# axiom_beta_sensor_cmv12000_v0_9_d0ae0354.net
KiCad netlist of a schematic drawn in EAGLE
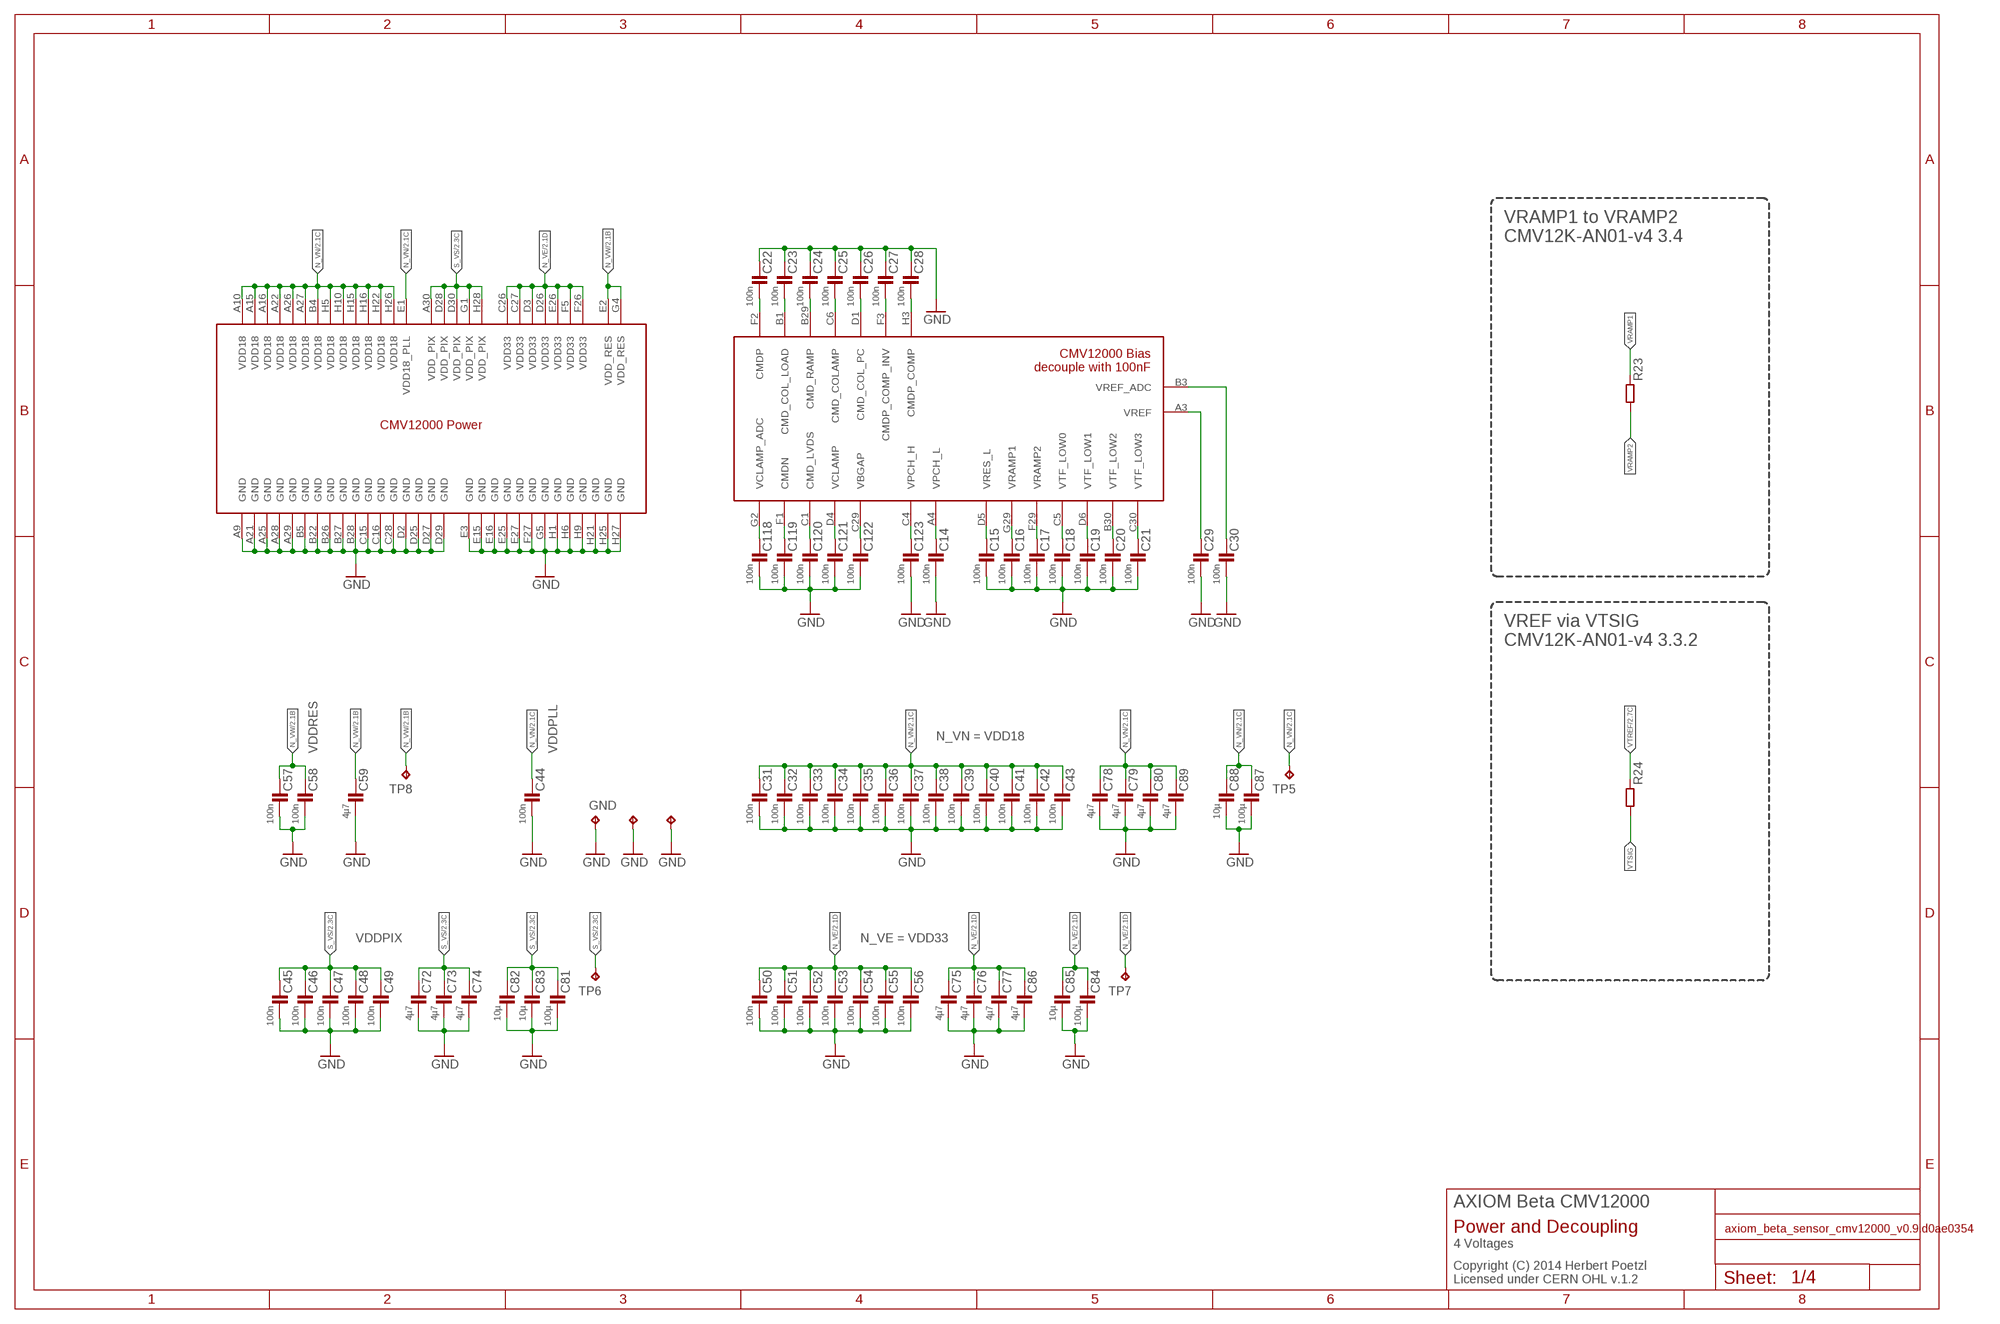
[diagram p0: schematic, sheet 1]
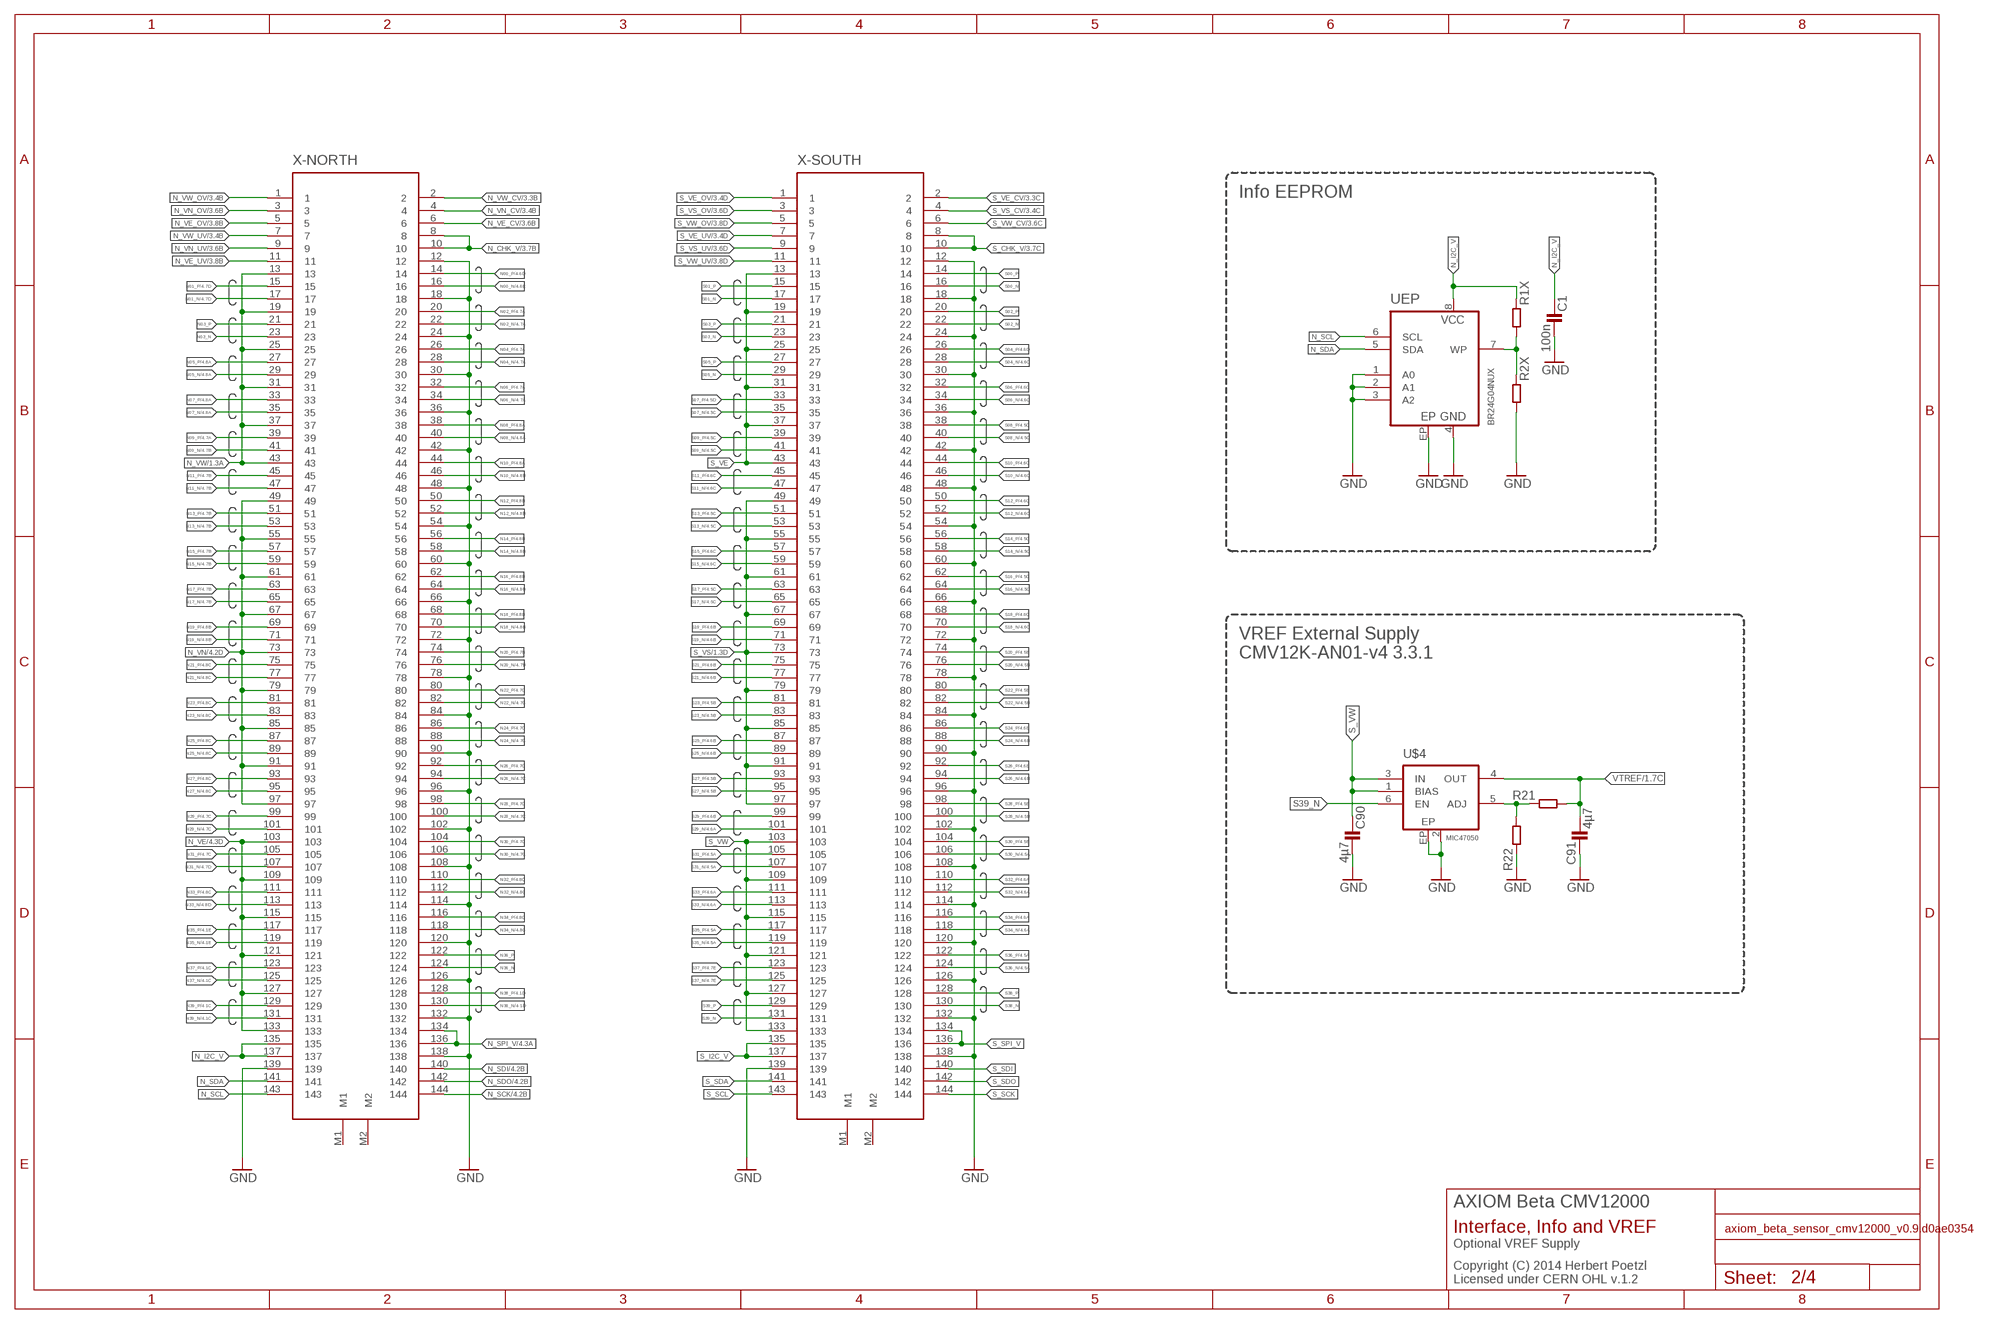
[diagram p1: schematic, sheet 2]
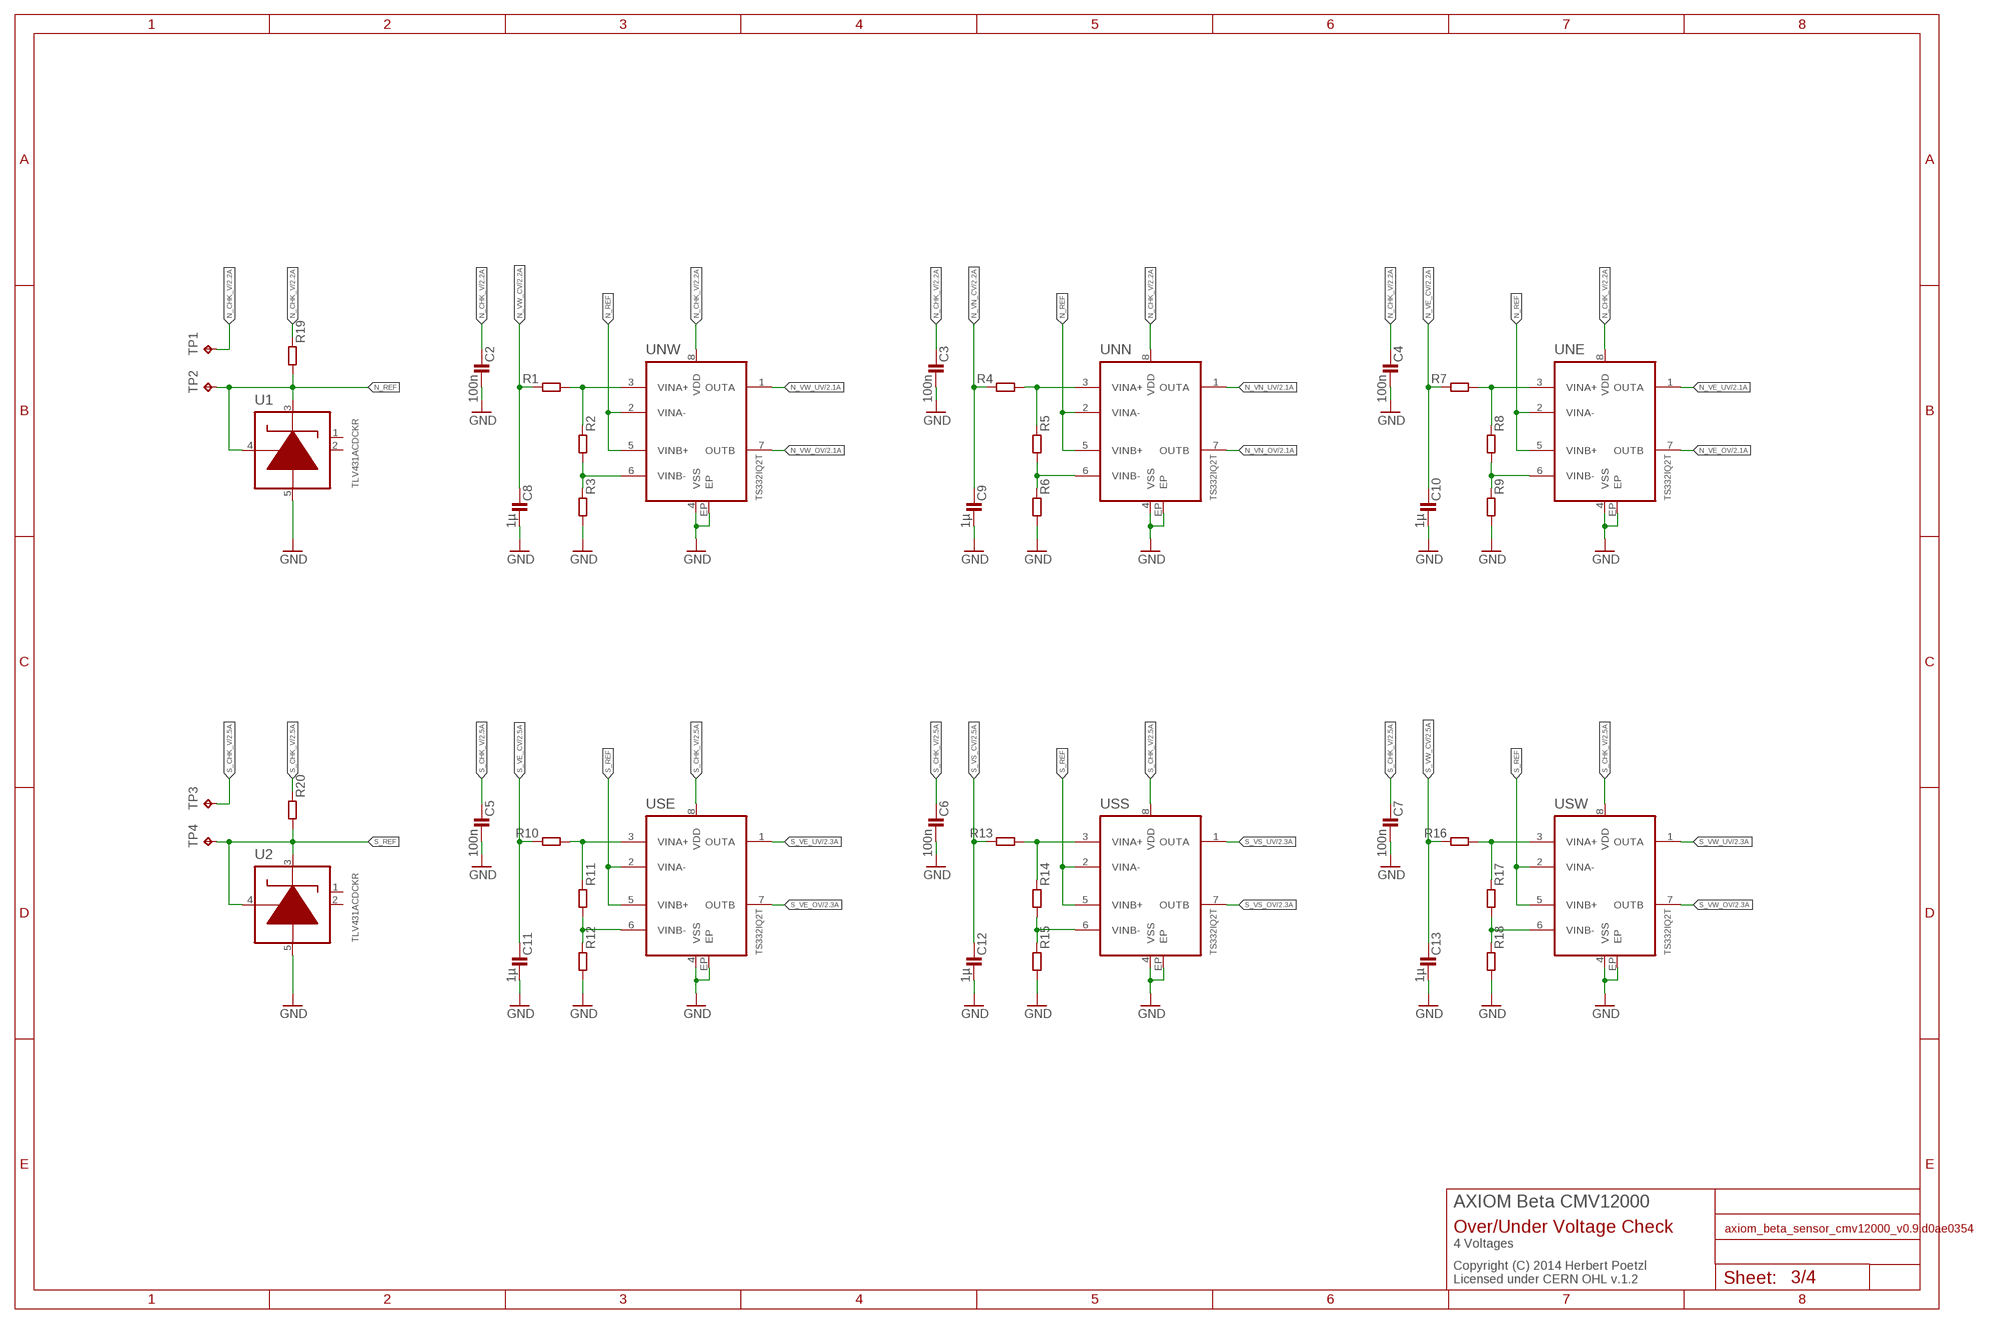
[diagram p2: schematic, sheet 3]
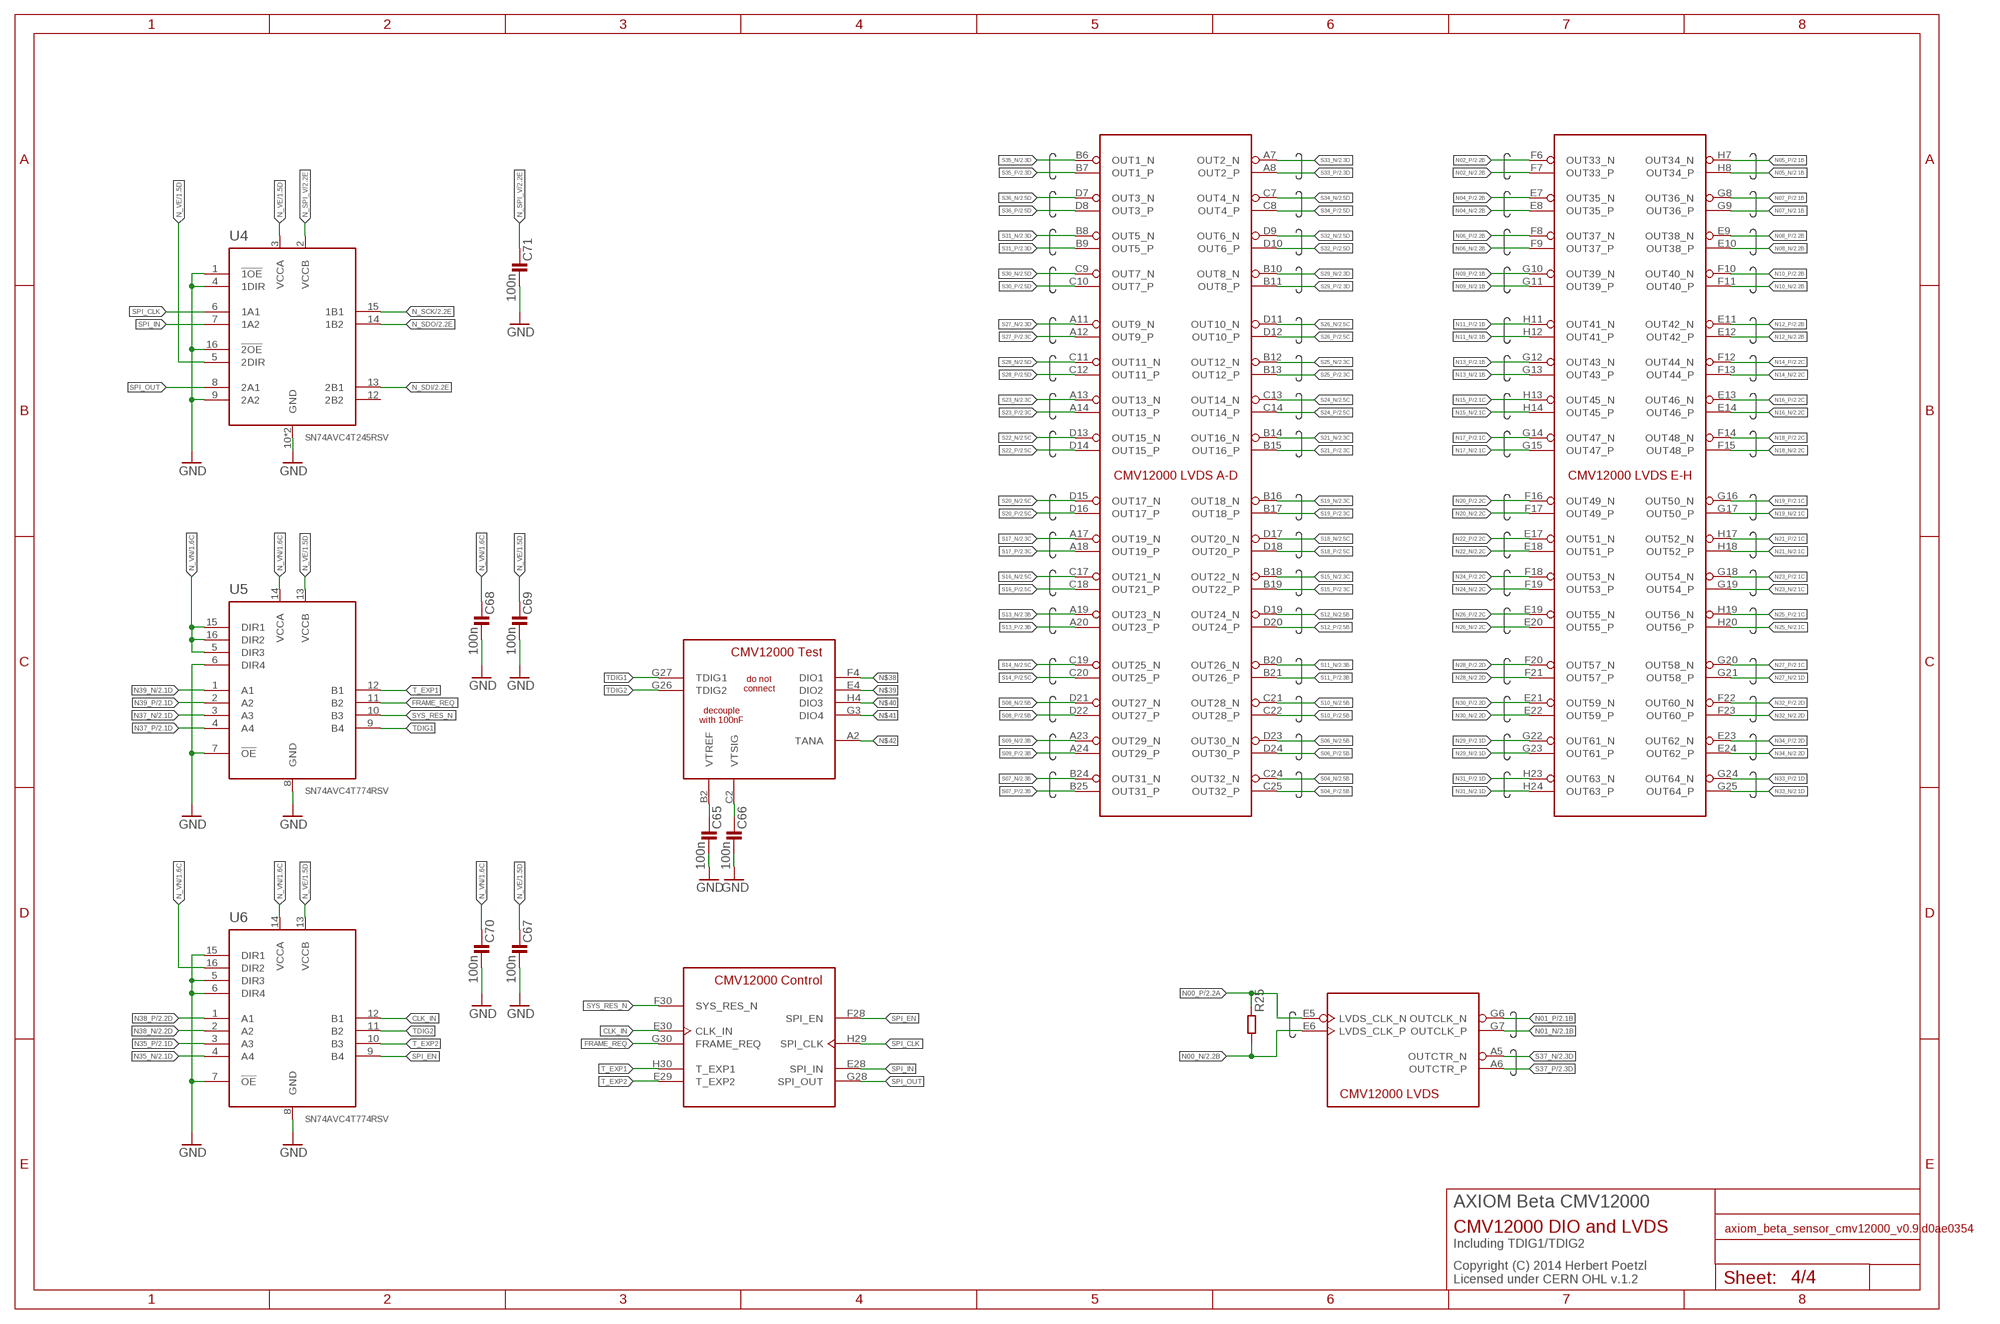
[diagram p3: schematic, sheet 4]

(export (version "E")
  (design (tool "Eeschema 10.0.6"))
  (components
    (comp (ref "C2")
      (value "100n")
      (footprint "eagle-import:0402-C")
      (libsource (lib "eagle-import") (part "C0402-C"))
    )
    (comp (ref "C3")
      (value "100n")
      (footprint "eagle-import:0402-C")
      (libsource (lib "eagle-import") (part "C0402-C"))
    )
    (comp (ref "C4")
      (value "100n")
      (footprint "eagle-import:0402-C")
      (libsource (lib "eagle-import") (part "C0402-C"))
    )
    (comp (ref "C5")
      (value "100n")
      (footprint "eagle-import:0402-C")
      (libsource (lib "eagle-import") (part "C0402-C"))
    )
    (comp (ref "C6")
      (value "100n")
      (footprint "eagle-import:0402-C")
      (libsource (lib "eagle-import") (part "C0402-C"))
    )
    (comp (ref "C7")
      (value "100n")
      (footprint "eagle-import:0402-C")
      (libsource (lib "eagle-import") (part "C0402-C"))
    )
    (comp (ref "C8")
      (value "1µ")
      (footprint "eagle-import:0402-C")
      (libsource (lib "eagle-import") (part "C0402-C"))
    )
    (comp (ref "C9")
      (value "1µ")
      (footprint "eagle-import:0402-C")
      (libsource (lib "eagle-import") (part "C0402-C"))
    )
    (comp (ref "C10")
      (value "1µ")
      (footprint "eagle-import:0402-C")
      (libsource (lib "eagle-import") (part "C0402-C"))
    )
    (comp (ref "C11")
      (value "1µ")
      (footprint "eagle-import:0402-C")
      (libsource (lib "eagle-import") (part "C0402-C"))
    )
    (comp (ref "C12")
      (value "1µ")
      (footprint "eagle-import:0402-C")
      (libsource (lib "eagle-import") (part "C0402-C"))
    )
    (comp (ref "C13")
      (value "1µ")
      (footprint "eagle-import:0402-C")
      (libsource (lib "eagle-import") (part "C0402-C"))
    )
    (comp (ref "R1")
      (value "R0402-C")
      (footprint "eagle-import:0402-C")
      (libsource (lib "eagle-import") (part "R0402-C"))
    )
    (comp (ref "R2")
      (value "R0402-C")
      (footprint "eagle-import:0402-C")
      (libsource (lib "eagle-import") (part "R0402-C"))
    )
    (comp (ref "R3")
      (value "R0402-C")
      (footprint "eagle-import:0402-C")
      (libsource (lib "eagle-import") (part "R0402-C"))
    )
    (comp (ref "R4")
      (value "R0402-C")
      (footprint "eagle-import:0402-C")
      (libsource (lib "eagle-import") (part "R0402-C"))
    )
    (comp (ref "R5")
      (value "R0402-C")
      (footprint "eagle-import:0402-C")
      (libsource (lib "eagle-import") (part "R0402-C"))
    )
    (comp (ref "R6")
      (value "R0402-C")
      (footprint "eagle-import:0402-C")
      (libsource (lib "eagle-import") (part "R0402-C"))
    )
    (comp (ref "R7")
      (value "R0402-C")
      (footprint "eagle-import:0402-C")
      (libsource (lib "eagle-import") (part "R0402-C"))
    )
    (comp (ref "R8")
      (value "R0402-C")
      (footprint "eagle-import:0402-C")
      (libsource (lib "eagle-import") (part "R0402-C"))
    )
    (comp (ref "R9")
      (value "R0402-C")
      (footprint "eagle-import:0402-C")
      (libsource (lib "eagle-import") (part "R0402-C"))
    )
    (comp (ref "R10")
      (value "R0402-C")
      (footprint "eagle-import:0402-C")
      (libsource (lib "eagle-import") (part "R0402-C"))
    )
    (comp (ref "R11")
      (value "R0402-C")
      (footprint "eagle-import:0402-C")
      (libsource (lib "eagle-import") (part "R0402-C"))
    )
    (comp (ref "R12")
      (value "R0402-C")
      (footprint "eagle-import:0402-C")
      (libsource (lib "eagle-import") (part "R0402-C"))
    )
    (comp (ref "R13")
      (value "R0402-C")
      (footprint "eagle-import:0402-C")
      (libsource (lib "eagle-import") (part "R0402-C"))
    )
    (comp (ref "R14")
      (value "R0402-C")
      (footprint "eagle-import:0402-C")
      (libsource (lib "eagle-import") (part "R0402-C"))
    )
    (comp (ref "R15")
      (value "R0402-C")
      (footprint "eagle-import:0402-C")
      (libsource (lib "eagle-import") (part "R0402-C"))
    )
    (comp (ref "R16")
      (value "R0402-C")
      (footprint "eagle-import:0402-C")
      (libsource (lib "eagle-import") (part "R0402-C"))
    )
    (comp (ref "R17")
      (value "R0402-C")
      (footprint "eagle-import:0402-C")
      (libsource (lib "eagle-import") (part "R0402-C"))
    )
    (comp (ref "R18")
      (value "R0402-C")
      (footprint "eagle-import:0402-C")
      (libsource (lib "eagle-import") (part "R0402-C"))
    )
    (comp (ref "R19")
      (value "R0402-C")
      (footprint "eagle-import:0402-C")
      (libsource (lib "eagle-import") (part "R0402-C"))
    )
    (comp (ref "R20")
      (value "R0402-C")
      (footprint "eagle-import:0402-C")
      (libsource (lib "eagle-import") (part "R0402-C"))
    )
    (comp (ref "TP1")
      (value "TPTP10R")
      (footprint "eagle-import:TP10R")
      (libsource (lib "eagle-import") (part "TPTP10R"))
    )
    (comp (ref "TP2")
      (value "TPTP10R")
      (footprint "eagle-import:TP10R")
      (libsource (lib "eagle-import") (part "TPTP10R"))
    )
    (comp (ref "TP3")
      (value "TPTP10R")
      (footprint "eagle-import:TP10R")
      (libsource (lib "eagle-import") (part "TPTP10R"))
    )
    (comp (ref "TP4")
      (value "TPTP10R")
      (footprint "eagle-import:TP10R")
      (libsource (lib "eagle-import") (part "TPTP10R"))
    )
    (comp (ref "U1")
      (value "TLV431ACDCKR")
      (footprint "eagle-import:SOT65P210X110-5N")
      (libsource (lib "eagle-import") (part "TLV431ACDCKR"))
    )
    (comp (ref "U2")
      (value "TLV431ACDCKR")
      (footprint "eagle-import:SOT65P210X110-5N")
      (libsource (lib "eagle-import") (part "TLV431ACDCKR"))
    )
    (comp (ref "UNE")
      (value "TS332IQ2T")
      (footprint "eagle-import:DFN200X200X100-9N")
      (libsource (lib "eagle-import") (part "TS332IQ2T"))
    )
    (comp (ref "UNN")
      (value "TS332IQ2T")
      (footprint "eagle-import:DFN200X200X100-9N")
      (libsource (lib "eagle-import") (part "TS332IQ2T"))
    )
    (comp (ref "UNW")
      (value "TS332IQ2T")
      (footprint "eagle-import:DFN200X200X100-9N")
      (libsource (lib "eagle-import") (part "TS332IQ2T"))
    )
    (comp (ref "USE")
      (value "TS332IQ2T")
      (footprint "eagle-import:DFN200X200X100-9N")
      (libsource (lib "eagle-import") (part "TS332IQ2T"))
    )
    (comp (ref "USS")
      (value "TS332IQ2T")
      (footprint "eagle-import:DFN200X200X100-9N")
      (libsource (lib "eagle-import") (part "TS332IQ2T"))
    )
    (comp (ref "USW")
      (value "TS332IQ2T")
      (footprint "eagle-import:DFN200X200X100-9N")
      (libsource (lib "eagle-import") (part "TS332IQ2T"))
    )
    (comp (ref "C65")
      (value "100n")
      (footprint "eagle-import:0402-C")
      (libsource (lib "eagle-import") (part "C0402-C"))
    )
    (comp (ref "C66")
      (value "100n")
      (footprint "eagle-import:0402-C")
      (libsource (lib "eagle-import") (part "C0402-C"))
    )
    (comp (ref "C67")
      (value "100n")
      (footprint "eagle-import:0402-C")
      (libsource (lib "eagle-import") (part "C0402-C"))
    )
    (comp (ref "C68")
      (value "100n")
      (footprint "eagle-import:0402-C")
      (libsource (lib "eagle-import") (part "C0402-C"))
    )
    (comp (ref "C69")
      (value "100n")
      (footprint "eagle-import:0402-C")
      (libsource (lib "eagle-import") (part "C0402-C"))
    )
    (comp (ref "C70")
      (value "100n")
      (footprint "eagle-import:0402-C")
      (libsource (lib "eagle-import") (part "C0402-C"))
    )
    (comp (ref "C71")
      (value "100n")
      (footprint "eagle-import:0402-C")
      (libsource (lib "eagle-import") (part "C0402-C"))
    )
    (comp (ref "R25")
      (value "R0402-C")
      (footprint "eagle-import:0402-C")
      (libsource (lib "eagle-import") (part "R0402-C"))
    )
    (comp (ref "U$2")
      (value "CMV12000ANDON")
      (footprint "eagle-import:10-30-07-237-400T4")
      (libsource (lib "eagle-import") (part "CMV12000ANDON"))
    )
    (comp (ref "U4")
      (value "SN74AVC4T245RSV")
      (footprint "eagle-import:QFN40P185X265X55-16N")
      (libsource (lib "eagle-import") (part "SN74AVC4T245RSV"))
    )
    (comp (ref "U5")
      (value "SN74AVC4T774RSV")
      (footprint "eagle-import:QFN40P185X265X55-16N")
      (libsource (lib "eagle-import") (part "SN74AVC4T774RSV"))
    )
    (comp (ref "U6")
      (value "SN74AVC4T774RSV")
      (footprint "eagle-import:QFN40P185X265X55-16N")
      (libsource (lib "eagle-import") (part "SN74AVC4T774RSV"))
    )
    (comp (ref "C1")
      (value "100n")
      (footprint "eagle-import:0402-C")
      (libsource (lib "eagle-import") (part "C0402-C"))
    )
    (comp (ref "C90")
      (value "4µ7")
      (footprint "eagle-import:0402-C")
      (libsource (lib "eagle-import") (part "C0402-C"))
    )
    (comp (ref "C91")
      (value "4µ7")
      (footprint "eagle-import:0402-C")
      (libsource (lib "eagle-import") (part "C0402-C"))
    )
    (comp (ref "R1X")
      (value "R0402-C")
      (footprint "eagle-import:0402-C")
      (libsource (lib "eagle-import") (part "R0402-C"))
    )
    (comp (ref "R2X")
      (value "R0402-C")
      (footprint "eagle-import:0402-C")
      (libsource (lib "eagle-import") (part "R0402-C"))
    )
    (comp (ref "R21")
      (value "R0402-C")
      (footprint "eagle-import:0402-C")
      (libsource (lib "eagle-import") (part "R0402-C"))
    )
    (comp (ref "R22")
      (value "R0402-C")
      (footprint "eagle-import:0402-C")
      (libsource (lib "eagle-import") (part "R0402-C"))
    )
    (comp (ref "U$4")
      (value "MIC47050")
      (footprint "eagle-import:MLF-6")
      (libsource (lib "eagle-import") (part "MIC47050-ADJ"))
    )
    (comp (ref "UEP")
      (value "BR24G04NUX")
      (footprint "eagle-import:DFN200X300X100-9N")
      (libsource (lib "eagle-import") (part "BR24G04NUX"))
    )
    (comp (ref "X-NORTH")
      (value "FX10-144P")
      (footprint "eagle-import:FX10A-144P")
      (libsource (lib "eagle-import") (part "FX10-144P"))
    )
    (comp (ref "X-SOUTH")
      (value "FX10-144P")
      (footprint "eagle-import:FX10A-144P")
      (libsource (lib "eagle-import") (part "FX10-144P"))
    )
    (comp (ref "C14")
      (value "100n")
      (footprint "eagle-import:0402-C")
      (libsource (lib "eagle-import") (part "C0402-C"))
    )
    (comp (ref "C15")
      (value "100n")
      (footprint "eagle-import:0402-C")
      (libsource (lib "eagle-import") (part "C0402-C"))
    )
    (comp (ref "C16")
      (value "100n")
      (footprint "eagle-import:0402-C")
      (libsource (lib "eagle-import") (part "C0402-C"))
    )
    (comp (ref "C17")
      (value "100n")
      (footprint "eagle-import:0402-C")
      (libsource (lib "eagle-import") (part "C0402-C"))
    )
    (comp (ref "C18")
      (value "100n")
      (footprint "eagle-import:0402-C")
      (libsource (lib "eagle-import") (part "C0402-C"))
    )
    (comp (ref "C19")
      (value "100n")
      (footprint "eagle-import:0402-C")
      (libsource (lib "eagle-import") (part "C0402-C"))
    )
    (comp (ref "C20")
      (value "100n")
      (footprint "eagle-import:0402-C")
      (libsource (lib "eagle-import") (part "C0402-C"))
    )
    (comp (ref "C21")
      (value "100n")
      (footprint "eagle-import:0402-C")
      (libsource (lib "eagle-import") (part "C0402-C"))
    )
    (comp (ref "C22")
      (value "100n")
      (footprint "eagle-import:0402-C")
      (libsource (lib "eagle-import") (part "C0402-C"))
    )
    (comp (ref "C23")
      (value "100n")
      (footprint "eagle-import:0402-C")
      (libsource (lib "eagle-import") (part "C0402-C"))
    )
    (comp (ref "C24")
      (value "100n")
      (footprint "eagle-import:0402-C")
      (libsource (lib "eagle-import") (part "C0402-C"))
    )
    (comp (ref "C25")
      (value "100n")
      (footprint "eagle-import:0402-C")
      (libsource (lib "eagle-import") (part "C0402-C"))
    )
    (comp (ref "C26")
      (value "100n")
      (footprint "eagle-import:0402-C")
      (libsource (lib "eagle-import") (part "C0402-C"))
    )
    (comp (ref "C27")
      (value "100n")
      (footprint "eagle-import:0402-C")
      (libsource (lib "eagle-import") (part "C0402-C"))
    )
    (comp (ref "C28")
      (value "100n")
      (footprint "eagle-import:0402-C")
      (libsource (lib "eagle-import") (part "C0402-C"))
    )
    (comp (ref "C29")
      (value "100n")
      (footprint "eagle-import:0402-C")
      (libsource (lib "eagle-import") (part "C0402-C"))
    )
    (comp (ref "C30")
      (value "100n")
      (footprint "eagle-import:0402-C")
      (libsource (lib "eagle-import") (part "C0402-C"))
    )
    (comp (ref "C31")
      (value "100n")
      (footprint "eagle-import:0402-C")
      (libsource (lib "eagle-import") (part "C0402-C"))
    )
    (comp (ref "C32")
      (value "100n")
      (footprint "eagle-import:0402-C")
      (libsource (lib "eagle-import") (part "C0402-C"))
    )
    (comp (ref "C33")
      (value "100n")
      (footprint "eagle-import:0402-C")
      (libsource (lib "eagle-import") (part "C0402-C"))
    )
    (comp (ref "C34")
      (value "100n")
      (footprint "eagle-import:0402-C")
      (libsource (lib "eagle-import") (part "C0402-C"))
    )
    (comp (ref "C35")
      (value "100n")
      (footprint "eagle-import:0402-C")
      (libsource (lib "eagle-import") (part "C0402-C"))
    )
    (comp (ref "C36")
      (value "100n")
      (footprint "eagle-import:0402-C")
      (libsource (lib "eagle-import") (part "C0402-C"))
    )
    (comp (ref "C37")
      (value "100n")
      (footprint "eagle-import:0402-C")
      (libsource (lib "eagle-import") (part "C0402-C"))
    )
    (comp (ref "C38")
      (value "100n")
      (footprint "eagle-import:0402-C")
      (libsource (lib "eagle-import") (part "C0402-C"))
    )
    (comp (ref "C39")
      (value "100n")
      (footprint "eagle-import:0402-C")
      (libsource (lib "eagle-import") (part "C0402-C"))
    )
    (comp (ref "C40")
      (value "100n")
      (footprint "eagle-import:0402-C")
      (libsource (lib "eagle-import") (part "C0402-C"))
    )
    (comp (ref "C41")
      (value "100n")
      (footprint "eagle-import:0402-C")
      (libsource (lib "eagle-import") (part "C0402-C"))
    )
    (comp (ref "C42")
      (value "100n")
      (footprint "eagle-import:0402-C")
      (libsource (lib "eagle-import") (part "C0402-C"))
    )
    (comp (ref "C43")
      (value "100n")
      (footprint "eagle-import:0402-C")
      (libsource (lib "eagle-import") (part "C0402-C"))
    )
    (comp (ref "C44")
      (value "100n")
      (footprint "eagle-import:0402-C")
      (libsource (lib "eagle-import") (part "C0402-C"))
    )
    (comp (ref "C45")
      (value "100n")
      (footprint "eagle-import:0402-C")
      (libsource (lib "eagle-import") (part "C0402-C"))
    )
    (comp (ref "C46")
      (value "100n")
      (footprint "eagle-import:0402-C")
      (libsource (lib "eagle-import") (part "C0402-C"))
    )
    (comp (ref "C47")
      (value "100n")
      (footprint "eagle-import:0402-C")
      (libsource (lib "eagle-import") (part "C0402-C"))
    )
    (comp (ref "C48")
      (value "100n")
      (footprint "eagle-import:0402-C")
      (libsource (lib "eagle-import") (part "C0402-C"))
    )
    (comp (ref "C49")
      (value "100n")
      (footprint "eagle-import:0402-C")
      (libsource (lib "eagle-import") (part "C0402-C"))
    )
    (comp (ref "C50")
      (value "100n")
      (footprint "eagle-import:0402-C")
      (libsource (lib "eagle-import") (part "C0402-C"))
    )
    (comp (ref "C51")
      (value "100n")
      (footprint "eagle-import:0402-C")
      (libsource (lib "eagle-import") (part "C0402-C"))
    )
    (comp (ref "C52")
      (value "100n")
      (footprint "eagle-import:0402-C")
      (libsource (lib "eagle-import") (part "C0402-C"))
    )
    (comp (ref "C53")
      (value "100n")
      (footprint "eagle-import:0402-C")
      (libsource (lib "eagle-import") (part "C0402-C"))
    )
    (comp (ref "C54")
      (value "100n")
      (footprint "eagle-import:0402-C")
      (libsource (lib "eagle-import") (part "C0402-C"))
    )
    (comp (ref "C55")
      (value "100n")
      (footprint "eagle-import:0402-C")
      (libsource (lib "eagle-import") (part "C0402-C"))
    )
    (comp (ref "C56")
      (value "100n")
      (footprint "eagle-import:0402-C")
      (libsource (lib "eagle-import") (part "C0402-C"))
    )
    (comp (ref "C57")
      (value "100n")
      (footprint "eagle-import:0402-C")
      (libsource (lib "eagle-import") (part "C0402-C"))
    )
    (comp (ref "C58")
      (value "100n")
      (footprint "eagle-import:0402-C")
      (libsource (lib "eagle-import") (part "C0402-C"))
    )
    (comp (ref "C59")
      (value "4µ7")
      (footprint "eagle-import:0402-C")
      (libsource (lib "eagle-import") (part "C0402-C"))
    )
    (comp (ref "C72")
      (value "4µ7")
      (footprint "eagle-import:0402-B")
      (libsource (lib "eagle-import") (part "C0402-B"))
    )
    (comp (ref "C73")
      (value "4µ7")
      (footprint "eagle-import:0402-C")
      (libsource (lib "eagle-import") (part "C0402-C"))
    )
    (comp (ref "C74")
      (value "4µ7")
      (footprint "eagle-import:0402-C")
      (libsource (lib "eagle-import") (part "C0402-C"))
    )
    (comp (ref "C75")
      (value "4µ7")
      (footprint "eagle-import:0402-C")
      (libsource (lib "eagle-import") (part "C0402-C"))
    )
    (comp (ref "C76")
      (value "4µ7")
      (footprint "eagle-import:0402-C")
      (libsource (lib "eagle-import") (part "C0402-C"))
    )
    (comp (ref "C77")
      (value "4µ7")
      (footprint "eagle-import:0402-B")
      (libsource (lib "eagle-import") (part "C0402-B"))
    )
    (comp (ref "C78")
      (value "4µ7")
      (footprint "eagle-import:0402-B")
      (libsource (lib "eagle-import") (part "C0402-B"))
    )
    (comp (ref "C79")
      (value "4µ7")
      (footprint "eagle-import:0402-C")
      (libsource (lib "eagle-import") (part "C0402-C"))
    )
    (comp (ref "C80")
      (value "4µ7")
      (footprint "eagle-import:0402-C")
      (libsource (lib "eagle-import") (part "C0402-C"))
    )
    (comp (ref "C81")
      (value "100µ")
      (footprint "eagle-import:1206-B")
      (libsource (lib "eagle-import") (part "C1206-B"))
    )
    (comp (ref "C82")
      (value "10µ")
      (footprint "eagle-import:0603-C")
      (libsource (lib "eagle-import") (part "C0603-C"))
    )
    (comp (ref "C83")
      (value "10µ")
      (footprint "eagle-import:0603-C")
      (libsource (lib "eagle-import") (part "C0603-C"))
    )
    (comp (ref "C84")
      (value "100µ")
      (footprint "eagle-import:1206-B")
      (libsource (lib "eagle-import") (part "C1206-B"))
    )
    (comp (ref "C85")
      (value "10µ")
      (footprint "eagle-import:0603-C")
      (libsource (lib "eagle-import") (part "C0603-C"))
    )
    (comp (ref "C86")
      (value "4µ7")
      (footprint "eagle-import:0402-C")
      (libsource (lib "eagle-import") (part "C0402-C"))
    )
    (comp (ref "C87")
      (value "100µ")
      (footprint "eagle-import:1206-B")
      (libsource (lib "eagle-import") (part "C1206-B"))
    )
    (comp (ref "C88")
      (value "10µ")
      (footprint "eagle-import:0603-C")
      (libsource (lib "eagle-import") (part "C0603-C"))
    )
    (comp (ref "C89")
      (value "4µ7")
      (footprint "eagle-import:0402-C")
      (libsource (lib "eagle-import") (part "C0402-C"))
    )
    (comp (ref "C118")
      (value "100n")
      (footprint "eagle-import:0402-C")
      (libsource (lib "eagle-import") (part "C0402-C"))
    )
    (comp (ref "C119")
      (value "100n")
      (footprint "eagle-import:0402-C")
      (libsource (lib "eagle-import") (part "C0402-C"))
    )
    (comp (ref "C120")
      (value "100n")
      (footprint "eagle-import:0402-C")
      (libsource (lib "eagle-import") (part "C0402-C"))
    )
    (comp (ref "C121")
      (value "100n")
      (footprint "eagle-import:0402-C")
      (libsource (lib "eagle-import") (part "C0402-C"))
    )
    (comp (ref "C122")
      (value "100n")
      (footprint "eagle-import:0402-C")
      (libsource (lib "eagle-import") (part "C0402-C"))
    )
    (comp (ref "C123")
      (value "100n")
      (footprint "eagle-import:0402-C")
      (libsource (lib "eagle-import") (part "C0402-C"))
    )
    (comp (ref "GND")
      (value "TPTP10R")
      (footprint "eagle-import:TP10R")
      (libsource (lib "eagle-import") (part "TPTP10R"))
    )
    (comp (ref "GND75")
      (value "TPTP10R")
      (footprint "eagle-import:TP10R")
      (libsource (lib "eagle-import") (part "TPTP10R"))
    )
    (comp (ref "GND77")
      (value "TPTP10R")
      (footprint "eagle-import:TP10R")
      (libsource (lib "eagle-import") (part "TPTP10R"))
    )
    (comp (ref "R23")
      (value "R0402-C")
      (footprint "eagle-import:0402-C")
      (libsource (lib "eagle-import") (part "R0402-C"))
    )
    (comp (ref "R24")
      (value "R0402-C")
      (footprint "eagle-import:0402-C")
      (libsource (lib "eagle-import") (part "R0402-C"))
    )
    (comp (ref "TP5")
      (value "TPTP10R")
      (footprint "eagle-import:TP10R")
      (libsource (lib "eagle-import") (part "TPTP10R"))
    )
    (comp (ref "TP6")
      (value "TPTP10R")
      (footprint "eagle-import:TP10R")
      (libsource (lib "eagle-import") (part "TPTP10R"))
    )
    (comp (ref "TP7")
      (value "TPTP10R")
      (footprint "eagle-import:TP10R")
      (libsource (lib "eagle-import") (part "TPTP10R"))
    )
    (comp (ref "TP8")
      (value "TPTP10R")
      (footprint "eagle-import:TP10R")
      (libsource (lib "eagle-import") (part "TPTP10R"))
    )
  )
  (nets
    (net (code "1") (name "CLK_IN") (class "Default")
      (node (ref "U$2") (pin "E30") (pinfunction "CLK_IN_E30") (pintype "input"))
      (node (ref "U6") (pin "12") (pinfunction "B1_12") (pintype "bidirectional"))
    )
    (net (code "2") (name "FRAME_REQ") (class "Default")
      (node (ref "U$2") (pin "G30") (pinfunction "FRAME_REQ_G30") (pintype "input"))
      (node (ref "U5") (pin "11") (pinfunction "B2_11") (pintype "bidirectional"))
    )
    (net (code "3") (name "GND") (class "Default")
      (node (ref "C1") (pin "2") (pinfunction "2_2") (pintype "passive"))
      (node (ref "C10") (pin "2") (pinfunction "2_2") (pintype "passive"))
      (node (ref "C11") (pin "2") (pinfunction "2_2") (pintype "passive"))
      (node (ref "C118") (pin "2") (pinfunction "2_2") (pintype "passive"))
      (node (ref "C119") (pin "2") (pinfunction "2_2") (pintype "passive"))
      (node (ref "C12") (pin "2") (pinfunction "2_2") (pintype "passive"))
      (node (ref "C120") (pin "2") (pinfunction "2_2") (pintype "passive"))
      (node (ref "C121") (pin "2") (pinfunction "2_2") (pintype "passive"))
      (node (ref "C122") (pin "2") (pinfunction "2_2") (pintype "passive"))
      (node (ref "C123") (pin "2") (pinfunction "2_2") (pintype "passive"))
      (node (ref "C13") (pin "2") (pinfunction "2_2") (pintype "passive"))
      (node (ref "C14") (pin "2") (pinfunction "2_2") (pintype "passive"))
      (node (ref "C15") (pin "2") (pinfunction "2_2") (pintype "passive"))
      (node (ref "C16") (pin "2") (pinfunction "2_2") (pintype "passive"))
      (node (ref "C17") (pin "2") (pinfunction "2_2") (pintype "passive"))
      (node (ref "C18") (pin "2") (pinfunction "2_2") (pintype "passive"))
      (node (ref "C19") (pin "2") (pinfunction "2_2") (pintype "passive"))
      (node (ref "C2") (pin "2") (pinfunction "2_2") (pintype "passive"))
      (node (ref "C20") (pin "2") (pinfunction "2_2") (pintype "passive"))
      (node (ref "C21") (pin "2") (pinfunction "2_2") (pintype "passive"))
      (node (ref "C22") (pin "1") (pinfunction "1_1") (pintype "passive"))
      (node (ref "C23") (pin "1") (pinfunction "1_1") (pintype "passive"))
      (node (ref "C24") (pin "1") (pinfunction "1_1") (pintype "passive"))
      (node (ref "C25") (pin "1") (pinfunction "1_1") (pintype "passive"))
      (node (ref "C26") (pin "1") (pinfunction "1_1") (pintype "passive"))
      (node (ref "C27") (pin "1") (pinfunction "1_1") (pintype "passive"))
      (node (ref "C28") (pin "1") (pinfunction "1_1") (pintype "passive"))
      (node (ref "C29") (pin "2") (pinfunction "2_2") (pintype "passive"))
      (node (ref "C3") (pin "2") (pinfunction "2_2") (pintype "passive"))
      (node (ref "C30") (pin "2") (pinfunction "2_2") (pintype "passive"))
      (node (ref "C31") (pin "2") (pinfunction "2_2") (pintype "passive"))
      (node (ref "C32") (pin "2") (pinfunction "2_2") (pintype "passive"))
      (node (ref "C33") (pin "2") (pinfunction "2_2") (pintype "passive"))
      (node (ref "C34") (pin "2") (pinfunction "2_2") (pintype "passive"))
      (node (ref "C35") (pin "2") (pinfunction "2_2") (pintype "passive"))
      (node (ref "C36") (pin "2") (pinfunction "2_2") (pintype "passive"))
      (node (ref "C37") (pin "2") (pinfunction "2_2") (pintype "passive"))
      (node (ref "C38") (pin "2") (pinfunction "2_2") (pintype "passive"))
      (node (ref "C39") (pin "2") (pinfunction "2_2") (pintype "passive"))
      (node (ref "C4") (pin "2") (pinfunction "2_2") (pintype "passive"))
      (node (ref "C40") (pin "2") (pinfunction "2_2") (pintype "passive"))
      (node (ref "C41") (pin "2") (pinfunction "2_2") (pintype "passive"))
      (node (ref "C42") (pin "2") (pinfunction "2_2") (pintype "passive"))
      (node (ref "C43") (pin "2") (pinfunction "2_2") (pintype "passive"))
      (node (ref "C44") (pin "2") (pinfunction "2_2") (pintype "passive"))
      (node (ref "C45") (pin "2") (pinfunction "2_2") (pintype "passive"))
      (node (ref "C46") (pin "2") (pinfunction "2_2") (pintype "passive"))
      (node (ref "C47") (pin "2") (pinfunction "2_2") (pintype "passive"))
      (node (ref "C48") (pin "2") (pinfunction "2_2") (pintype "passive"))
      (node (ref "C49") (pin "2") (pinfunction "2_2") (pintype "passive"))
      (node (ref "C5") (pin "2") (pinfunction "2_2") (pintype "passive"))
      (node (ref "C50") (pin "2") (pinfunction "2_2") (pintype "passive"))
      (node (ref "C51") (pin "2") (pinfunction "2_2") (pintype "passive"))
      (node (ref "C52") (pin "2") (pinfunction "2_2") (pintype "passive"))
      (node (ref "C53") (pin "2") (pinfunction "2_2") (pintype "passive"))
      (node (ref "C54") (pin "2") (pinfunction "2_2") (pintype "passive"))
      (node (ref "C55") (pin "2") (pinfunction "2_2") (pintype "passive"))
      (node (ref "C56") (pin "2") (pinfunction "2_2") (pintype "passive"))
      (node (ref "C57") (pin "2") (pinfunction "2_2") (pintype "passive"))
      (node (ref "C58") (pin "2") (pinfunction "2_2") (pintype "passive"))
      (node (ref "C59") (pin "2") (pinfunction "2_2") (pintype "passive"))
      (node (ref "C6") (pin "2") (pinfunction "2_2") (pintype "passive"))
      (node (ref "C65") (pin "2") (pinfunction "2_2") (pintype "passive"))
      (node (ref "C66") (pin "2") (pinfunction "2_2") (pintype "passive"))
      (node (ref "C67") (pin "2") (pinfunction "2_2") (pintype "passive"))
      (node (ref "C68") (pin "2") (pinfunction "2_2") (pintype "passive"))
      (node (ref "C69") (pin "2") (pinfunction "2_2") (pintype "passive"))
      (node (ref "C7") (pin "2") (pinfunction "2_2") (pintype "passive"))
      (node (ref "C70") (pin "2") (pinfunction "2_2") (pintype "passive"))
      (node (ref "C71") (pin "2") (pinfunction "2_2") (pintype "passive"))
      (node (ref "C72") (pin "2") (pinfunction "2_2") (pintype "passive"))
      (node (ref "C73") (pin "2") (pinfunction "2_2") (pintype "passive"))
      (node (ref "C74") (pin "2") (pinfunction "2_2") (pintype "passive"))
      (node (ref "C75") (pin "2") (pinfunction "2_2") (pintype "passive"))
      (node (ref "C76") (pin "2") (pinfunction "2_2") (pintype "passive"))
      (node (ref "C77") (pin "2") (pinfunction "2_2") (pintype "passive"))
      (node (ref "C78") (pin "2") (pinfunction "2_2") (pintype "passive"))
      (node (ref "C79") (pin "2") (pinfunction "2_2") (pintype "passive"))
      (node (ref "C8") (pin "2") (pinfunction "2_2") (pintype "passive"))
      (node (ref "C80") (pin "2") (pinfunction "2_2") (pintype "passive"))
      (node (ref "C81") (pin "2") (pinfunction "2_2") (pintype "passive"))
      (node (ref "C82") (pin "2") (pinfunction "2_2") (pintype "passive"))
      (node (ref "C83") (pin "2") (pinfunction "2_2") (pintype "passive"))
      (node (ref "C84") (pin "2") (pinfunction "2_2") (pintype "passive"))
      (node (ref "C85") (pin "2") (pinfunction "2_2") (pintype "passive"))
      (node (ref "C86") (pin "2") (pinfunction "2_2") (pintype "passive"))
      (node (ref "C87") (pin "2") (pinfunction "2_2") (pintype "passive"))
      (node (ref "C88") (pin "2") (pinfunction "2_2") (pintype "passive"))
      (node (ref "C89") (pin "2") (pinfunction "2_2") (pintype "passive"))
      (node (ref "C9") (pin "2") (pinfunction "2_2") (pintype "passive"))
      (node (ref "C90") (pin "2") (pinfunction "2_2") (pintype "passive"))
      (node (ref "C91") (pin "1") (pinfunction "1_1") (pintype "passive"))
      (node (ref "GND") (pin "TP") (pinfunction "TP_TP") (pintype "input"))
      (node (ref "GND75") (pin "TP") (pinfunction "TP_TP") (pintype "input"))
      (node (ref "GND77") (pin "TP") (pinfunction "TP_TP") (pintype "input"))
      (node (ref "R12") (pin "2") (pinfunction "2_2") (pintype "passive"))
      (node (ref "R15") (pin "2") (pinfunction "2_2") (pintype "passive"))
      (node (ref "R18") (pin "2") (pinfunction "2_2") (pintype "passive"))
      (node (ref "R22") (pin "1") (pinfunction "1_1") (pintype "passive"))
      (node (ref "R2X") (pin "2") (pinfunction "2_2") (pintype "passive"))
      (node (ref "R3") (pin "2") (pinfunction "2_2") (pintype "passive"))
      (node (ref "R6") (pin "2") (pinfunction "2_2") (pintype "passive"))
      (node (ref "R9") (pin "2") (pinfunction "2_2") (pintype "passive"))
      (node (ref "U$2") (pin "A21") (pinfunction "GND_A21") (pintype "power_in"))
      (node (ref "U$2") (pin "A25") (pinfunction "GND_A25") (pintype "power_in"))
      (node (ref "U$2") (pin "A28") (pinfunction "GND_A28") (pintype "power_in"))
      (node (ref "U$2") (pin "A29") (pinfunction "GND_A29") (pintype "power_in"))
      (node (ref "U$2") (pin "A9") (pinfunction "GND_A9") (pintype "power_in"))
      (node (ref "U$2") (pin "B22") (pinfunction "GND_B22") (pintype "power_in"))
      (node (ref "U$2") (pin "B26") (pinfunction "GND_B26") (pintype "power_in"))
      (node (ref "U$2") (pin "B27") (pinfunction "GND_B27") (pintype "power_in"))
      (node (ref "U$2") (pin "B28") (pinfunction "GND_B28") (pintype "power_in"))
      (node (ref "U$2") (pin "B5") (pinfunction "GND_B5") (pintype "power_in"))
      (node (ref "U$2") (pin "C15") (pinfunction "GND_C15") (pintype "power_in"))
      (node (ref "U$2") (pin "C16") (pinfunction "GND_C16") (pintype "power_in"))
      (node (ref "U$2") (pin "C28") (pinfunction "GND_C28") (pintype "power_in"))
      (node (ref "U$2") (pin "D2") (pinfunction "GND_D2") (pintype "power_in"))
      (node (ref "U$2") (pin "D25") (pinfunction "GND_D25") (pintype "power_in"))
      (node (ref "U$2") (pin "D27") (pinfunction "GND_D27") (pintype "power_in"))
      (node (ref "U$2") (pin "D29") (pinfunction "GND_D29") (pintype "power_in"))
      (node (ref "U$2") (pin "E15") (pinfunction "GND_E15") (pintype "power_in"))
      (node (ref "U$2") (pin "E16") (pinfunction "GND_E16") (pintype "power_in"))
      (node (ref "U$2") (pin "E25") (pinfunction "GND_E25") (pintype "power_in"))
      (node (ref "U$2") (pin "E27") (pinfunction "GND_E27") (pintype "power_in"))
      (node (ref "U$2") (pin "E3") (pinfunction "GND_E3") (pintype "power_in"))
      (node (ref "U$2") (pin "F27") (pinfunction "GND_F27") (pintype "power_in"))
      (node (ref "U$2") (pin "G5") (pinfunction "GND_G5") (pintype "power_in"))
      (node (ref "U$2") (pin "H1") (pinfunction "GND_H1") (pintype "power_in"))
      (node (ref "U$2") (pin "H21") (pinfunction "GND_H21") (pintype "power_in"))
      (node (ref "U$2") (pin "H25") (pinfunction "GND_H25") (pintype "power_in"))
      (node (ref "U$2") (pin "H27") (pinfunction "GND_H27") (pintype "power_in"))
      (node (ref "U$2") (pin "H6") (pinfunction "GND_H6") (pintype "power_in"))
      (node (ref "U$2") (pin "H9") (pinfunction "GND_H9") (pintype "power_in"))
      (node (ref "U$4") (pin "2") (pinfunction "GND_2") (pintype "power_in"))
      (node (ref "U$4") (pin "EP") (pinfunction "EP_EP") (pintype "power_in"))
      (node (ref "U1") (pin "5") (pinfunction "ANODE_5") (pintype "input"))
      (node (ref "U2") (pin "5") (pinfunction "ANODE_5") (pintype "input"))
      (node (ref "U4") (pin "1") (pinfunction "~{1OE}_1") (pintype "input"))
      (node (ref "U4") (pin "10") (pinfunction "GND_10") (pintype "passive"))
      (node (ref "U4") (pin "11") (pinfunction "GND_11") (pintype "passive"))
      (node (ref "U4") (pin "16") (pinfunction "~{2OE}_16") (pintype "input"))
      (node (ref "U4") (pin "4") (pinfunction "1DIR_4") (pintype "input"))
      (node (ref "U4") (pin "9") (pinfunction "2A2_9") (pintype "output"))
      (node (ref "U5") (pin "6") (pinfunction "DIR4_6") (pintype "input"))
      (node (ref "U5") (pin "7") (pinfunction "~{OE}_7") (pintype "input"))
      (node (ref "U5") (pin "8") (pinfunction "GND_8") (pintype "passive"))
      (node (ref "U6") (pin "15") (pinfunction "DIR1_15") (pintype "input"))
      (node (ref "U6") (pin "5") (pinfunction "DIR3_5") (pintype "input"))
      (node (ref "U6") (pin "6") (pinfunction "DIR4_6") (pintype "input"))
      (node (ref "U6") (pin "7") (pinfunction "~{OE}_7") (pintype "input"))
      (node (ref "U6") (pin "8") (pinfunction "GND_8") (pintype "passive"))
      (node (ref "UEP") (pin "1") (pinfunction "A0_1") (pintype "input"))
      (node (ref "UEP") (pin "2") (pinfunction "A1_2") (pintype "input"))
      (node (ref "UEP") (pin "3") (pinfunction "A2_3") (pintype "input"))
      (node (ref "UEP") (pin "4") (pinfunction "GND_4") (pintype "passive"))
      (node (ref "UEP") (pin "EP") (pinfunction "EP_EP") (pintype "passive"))
      (node (ref "UNE") (pin "4") (pinfunction "VSS_4") (pintype "power_in"))
      (node (ref "UNE") (pin "EP") (pinfunction "EP_EP") (pintype "passive"))
      (node (ref "UNN") (pin "4") (pinfunction "VSS_4") (pintype "power_in"))
      (node (ref "UNN") (pin "EP") (pinfunction "EP_EP") (pintype "passive"))
      (node (ref "UNW") (pin "4") (pinfunction "VSS_4") (pintype "power_in"))
      (node (ref "UNW") (pin "EP") (pinfunction "EP_EP") (pintype "passive"))
      (node (ref "USE") (pin "4") (pinfunction "VSS_4") (pintype "power_in"))
      (node (ref "USE") (pin "EP") (pinfunction "EP_EP") (pintype "passive"))
      (node (ref "USS") (pin "4") (pinfunction "VSS_4") (pintype "power_in"))
      (node (ref "USS") (pin "EP") (pinfunction "EP_EP") (pintype "passive"))
      (node (ref "USW") (pin "4") (pinfunction "VSS_4") (pintype "power_in"))
      (node (ref "USW") (pin "EP") (pinfunction "EP_EP") (pintype "passive"))
      (node (ref "X-NORTH") (pin "102") (pinfunction "102_102") (pintype "bidirectional"))
      (node (ref "X-NORTH") (pin "108") (pinfunction "108_108") (pintype "bidirectional"))
      (node (ref "X-NORTH") (pin "114") (pinfunction "114_114") (pintype "bidirectional"))
      (node (ref "X-NORTH") (pin "12") (pinfunction "12_12") (pintype "bidirectional"))
      (node (ref "X-NORTH") (pin "120") (pinfunction "120_120") (pintype "bidirectional"))
      (node (ref "X-NORTH") (pin "126") (pinfunction "126_126") (pintype "bidirectional"))
      (node (ref "X-NORTH") (pin "132") (pinfunction "132_132") (pintype "bidirectional"))
      (node (ref "X-NORTH") (pin "138") (pinfunction "138_138") (pintype "bidirectional"))
      (node (ref "X-NORTH") (pin "139") (pinfunction "139_139") (pintype "bidirectional"))
      (node (ref "X-NORTH") (pin "18") (pinfunction "18_18") (pintype "bidirectional"))
      (node (ref "X-NORTH") (pin "24") (pinfunction "24_24") (pintype "bidirectional"))
      (node (ref "X-NORTH") (pin "30") (pinfunction "30_30") (pintype "bidirectional"))
      (node (ref "X-NORTH") (pin "36") (pinfunction "36_36") (pintype "bidirectional"))
      (node (ref "X-NORTH") (pin "42") (pinfunction "42_42") (pintype "bidirectional"))
      (node (ref "X-NORTH") (pin "48") (pinfunction "48_48") (pintype "bidirectional"))
      (node (ref "X-NORTH") (pin "54") (pinfunction "54_54") (pintype "bidirectional"))
      (node (ref "X-NORTH") (pin "60") (pinfunction "60_60") (pintype "bidirectional"))
      (node (ref "X-NORTH") (pin "66") (pinfunction "66_66") (pintype "bidirectional"))
      (node (ref "X-NORTH") (pin "72") (pinfunction "72_72") (pintype "bidirectional"))
      (node (ref "X-NORTH") (pin "78") (pinfunction "78_78") (pintype "bidirectional"))
      (node (ref "X-NORTH") (pin "84") (pinfunction "84_84") (pintype "bidirectional"))
      (node (ref "X-NORTH") (pin "90") (pinfunction "90_90") (pintype "bidirectional"))
      (node (ref "X-NORTH") (pin "96") (pinfunction "96_96") (pintype "bidirectional"))
      (node (ref "X-SOUTH") (pin "102") (pinfunction "102_102") (pintype "bidirectional"))
      (node (ref "X-SOUTH") (pin "108") (pinfunction "108_108") (pintype "bidirectional"))
      (node (ref "X-SOUTH") (pin "114") (pinfunction "114_114") (pintype "bidirectional"))
      (node (ref "X-SOUTH") (pin "12") (pinfunction "12_12") (pintype "bidirectional"))
      (node (ref "X-SOUTH") (pin "120") (pinfunction "120_120") (pintype "bidirectional"))
      (node (ref "X-SOUTH") (pin "126") (pinfunction "126_126") (pintype "bidirectional"))
      (node (ref "X-SOUTH") (pin "132") (pinfunction "132_132") (pintype "bidirectional"))
      (node (ref "X-SOUTH") (pin "138") (pinfunction "138_138") (pintype "bidirectional"))
      (node (ref "X-SOUTH") (pin "139") (pinfunction "139_139") (pintype "bidirectional"))
      (node (ref "X-SOUTH") (pin "18") (pinfunction "18_18") (pintype "bidirectional"))
      (node (ref "X-SOUTH") (pin "24") (pinfunction "24_24") (pintype "bidirectional"))
      (node (ref "X-SOUTH") (pin "30") (pinfunction "30_30") (pintype "bidirectional"))
      (node (ref "X-SOUTH") (pin "36") (pinfunction "36_36") (pintype "bidirectional"))
      (node (ref "X-SOUTH") (pin "42") (pinfunction "42_42") (pintype "bidirectional"))
      (node (ref "X-SOUTH") (pin "48") (pinfunction "48_48") (pintype "bidirectional"))
      (node (ref "X-SOUTH") (pin "54") (pinfunction "54_54") (pintype "bidirectional"))
      (node (ref "X-SOUTH") (pin "60") (pinfunction "60_60") (pintype "bidirectional"))
      (node (ref "X-SOUTH") (pin "66") (pinfunction "66_66") (pintype "bidirectional"))
      (node (ref "X-SOUTH") (pin "72") (pinfunction "72_72") (pintype "bidirectional"))
      (node (ref "X-SOUTH") (pin "78") (pinfunction "78_78") (pintype "bidirectional"))
      (node (ref "X-SOUTH") (pin "84") (pinfunction "84_84") (pintype "bidirectional"))
      (node (ref "X-SOUTH") (pin "90") (pinfunction "90_90") (pintype "bidirectional"))
      (node (ref "X-SOUTH") (pin "96") (pinfunction "96_96") (pintype "bidirectional"))
    )
    (net (code "4") (name "N$38") (class "Default")
      (node (ref "U$2") (pin "F4") (pinfunction "DIO1_F4") (pintype "output"))
    )
    (net (code "5") (name "N$39") (class "Default")
      (node (ref "U$2") (pin "E4") (pinfunction "DIO2_E4") (pintype "output"))
    )
    (net (code "6") (name "N$40") (class "Default")
      (node (ref "U$2") (pin "H4") (pinfunction "DIO3_H4") (pintype "output"))
    )
    (net (code "7") (name "N$41") (class "Default")
      (node (ref "U$2") (pin "G3") (pinfunction "DIO4_G3") (pintype "output"))
    )
    (net (code "8") (name "N$42") (class "Default")
      (node (ref "U$2") (pin "A2") (pinfunction "TANA_A2") (pintype "output"))
    )
    (net (code "9") (name "N00_N") (class "Default")
      (node (ref "R25") (pin "2") (pinfunction "2_2") (pintype "passive"))
      (node (ref "U$2") (pin "E6") (pinfunction "LVDS_CLK_P_E6") (pintype "input"))
      (node (ref "X-NORTH") (pin "16") (pinfunction "16_16") (pintype "bidirectional"))
    )
    (net (code "10") (name "N00_P") (class "Default")
      (node (ref "R25") (pin "1") (pinfunction "1_1") (pintype "passive"))
      (node (ref "U$2") (pin "E5") (pinfunction "LVDS_CLK_N_E5") (pintype "input"))
      (node (ref "X-NORTH") (pin "14") (pinfunction "14_14") (pintype "bidirectional"))
    )
    (net (code "11") (name "N01_N") (class "Default")
      (node (ref "U$2") (pin "G7") (pinfunction "OUTCLK_P_G7") (pintype "output"))
      (node (ref "X-NORTH") (pin "17") (pinfunction "17_17") (pintype "bidirectional"))
    )
    (net (code "12") (name "N01_P") (class "Default")
      (node (ref "U$2") (pin "G6") (pinfunction "OUTCLK_N_G6") (pintype "output"))
      (node (ref "X-NORTH") (pin "15") (pinfunction "15_15") (pintype "bidirectional"))
    )
    (net (code "13") (name "N02_N") (class "Default")
      (node (ref "U$2") (pin "F7") (pinfunction "OUT33_P_F7") (pintype "output"))
      (node (ref "X-NORTH") (pin "22") (pinfunction "22_22") (pintype "bidirectional"))
    )
    (net (code "14") (name "N02_P") (class "Default")
      (node (ref "U$2") (pin "F6") (pinfunction "OUT33_N_F6") (pintype "output"))
      (node (ref "X-NORTH") (pin "20") (pinfunction "20_20") (pintype "bidirectional"))
    )
    (net (code "15") (name "N03_N") (class "Default")
      (node (ref "X-NORTH") (pin "23") (pinfunction "23_23") (pintype "bidirectional"))
    )
    (net (code "16") (name "N03_P") (class "Default")
      (node (ref "X-NORTH") (pin "21") (pinfunction "21_21") (pintype "bidirectional"))
    )
    (net (code "17") (name "N04_N") (class "Default")
      (node (ref "U$2") (pin "E8") (pinfunction "OUT35_P_E8") (pintype "output"))
      (node (ref "X-NORTH") (pin "28") (pinfunction "28_28") (pintype "bidirectional"))
    )
    (net (code "18") (name "N04_P") (class "Default")
      (node (ref "U$2") (pin "E7") (pinfunction "OUT35_N_E7") (pintype "output"))
      (node (ref "X-NORTH") (pin "26") (pinfunction "26_26") (pintype "bidirectional"))
    )
    (net (code "19") (name "N05_N") (class "Default")
      (node (ref "U$2") (pin "H8") (pinfunction "OUT34_P_H8") (pintype "output"))
      (node (ref "X-NORTH") (pin "29") (pinfunction "29_29") (pintype "bidirectional"))
    )
    (net (code "20") (name "N05_P") (class "Default")
      (node (ref "U$2") (pin "H7") (pinfunction "OUT34_N_H7") (pintype "output"))
      (node (ref "X-NORTH") (pin "27") (pinfunction "27_27") (pintype "bidirectional"))
    )
    (net (code "21") (name "N06_N") (class "Default")
      (node (ref "U$2") (pin "F9") (pinfunction "OUT37_P_F9") (pintype "output"))
      (node (ref "X-NORTH") (pin "34") (pinfunction "34_34") (pintype "bidirectional"))
    )
    (net (code "22") (name "N06_P") (class "Default")
      (node (ref "U$2") (pin "F8") (pinfunction "OUT37_N_F8") (pintype "output"))
      (node (ref "X-NORTH") (pin "32") (pinfunction "32_32") (pintype "bidirectional"))
    )
    (net (code "23") (name "N07_N") (class "Default")
      (node (ref "U$2") (pin "G9") (pinfunction "OUT36_P_G9") (pintype "output"))
      (node (ref "X-NORTH") (pin "35") (pinfunction "35_35") (pintype "bidirectional"))
    )
    (net (code "24") (name "N07_P") (class "Default")
      (node (ref "U$2") (pin "G8") (pinfunction "OUT36_N_G8") (pintype "output"))
      (node (ref "X-NORTH") (pin "33") (pinfunction "33_33") (pintype "bidirectional"))
    )
    (net (code "25") (name "N08_N") (class "Default")
      (node (ref "U$2") (pin "E10") (pinfunction "OUT38_P_E10") (pintype "output"))
      (node (ref "X-NORTH") (pin "40") (pinfunction "40_40") (pintype "bidirectional"))
    )
    (net (code "26") (name "N08_P") (class "Default")
      (node (ref "U$2") (pin "E9") (pinfunction "OUT38_N_E9") (pintype "output"))
      (node (ref "X-NORTH") (pin "38") (pinfunction "38_38") (pintype "bidirectional"))
    )
    (net (code "27") (name "N09_N") (class "Default")
      (node (ref "U$2") (pin "G11") (pinfunction "OUT39_P_G11") (pintype "output"))
      (node (ref "X-NORTH") (pin "41") (pinfunction "41_41") (pintype "bidirectional"))
    )
    (net (code "28") (name "N09_P") (class "Default")
      (node (ref "U$2") (pin "G10") (pinfunction "OUT39_N_G10") (pintype "output"))
      (node (ref "X-NORTH") (pin "39") (pinfunction "39_39") (pintype "bidirectional"))
    )
    (net (code "29") (name "N10_N") (class "Default")
      (node (ref "U$2") (pin "F11") (pinfunction "OUT40_P_F11") (pintype "output"))
      (node (ref "X-NORTH") (pin "46") (pinfunction "46_46") (pintype "bidirectional"))
    )
    (net (code "30") (name "N10_P") (class "Default")
      (node (ref "U$2") (pin "F10") (pinfunction "OUT40_N_F10") (pintype "output"))
      (node (ref "X-NORTH") (pin "44") (pinfunction "44_44") (pintype "bidirectional"))
    )
    (net (code "31") (name "N11_N") (class "Default")
      (node (ref "U$2") (pin "H12") (pinfunction "OUT41_P_H12") (pintype "output"))
      (node (ref "X-NORTH") (pin "47") (pinfunction "47_47") (pintype "bidirectional"))
    )
    (net (code "32") (name "N11_P") (class "Default")
      (node (ref "U$2") (pin "H11") (pinfunction "OUT41_N_H11") (pintype "output"))
      (node (ref "X-NORTH") (pin "45") (pinfunction "45_45") (pintype "bidirectional"))
    )
    (net (code "33") (name "N12_N") (class "Default")
      (node (ref "U$2") (pin "E12") (pinfunction "OUT42_P_E12") (pintype "output"))
      (node (ref "X-NORTH") (pin "52") (pinfunction "52_52") (pintype "bidirectional"))
    )
    (net (code "34") (name "N12_P") (class "Default")
      (node (ref "U$2") (pin "E11") (pinfunction "OUT42_N_E11") (pintype "output"))
      (node (ref "X-NORTH") (pin "50") (pinfunction "50_50") (pintype "bidirectional"))
    )
    (net (code "35") (name "N13_N") (class "Default")
      (node (ref "U$2") (pin "G13") (pinfunction "OUT43_P_G13") (pintype "output"))
      (node (ref "X-NORTH") (pin "53") (pinfunction "53_53") (pintype "bidirectional"))
    )
    (net (code "36") (name "N13_P") (class "Default")
      (node (ref "U$2") (pin "G12") (pinfunction "OUT43_N_G12") (pintype "output"))
      (node (ref "X-NORTH") (pin "51") (pinfunction "51_51") (pintype "bidirectional"))
    )
    (net (code "37") (name "N14_N") (class "Default")
      (node (ref "U$2") (pin "F13") (pinfunction "OUT44_P_F13") (pintype "output"))
      (node (ref "X-NORTH") (pin "58") (pinfunction "58_58") (pintype "bidirectional"))
    )
    (net (code "38") (name "N14_P") (class "Default")
      (node (ref "U$2") (pin "F12") (pinfunction "OUT44_N_F12") (pintype "output"))
      (node (ref "X-NORTH") (pin "56") (pinfunction "56_56") (pintype "bidirectional"))
    )
    (net (code "39") (name "N15_N") (class "Default")
      (node (ref "U$2") (pin "H14") (pinfunction "OUT45_P_H14") (pintype "output"))
      (node (ref "X-NORTH") (pin "59") (pinfunction "59_59") (pintype "bidirectional"))
    )
    (net (code "40") (name "N15_P") (class "Default")
      (node (ref "U$2") (pin "H13") (pinfunction "OUT45_N_H13") (pintype "output"))
      (node (ref "X-NORTH") (pin "57") (pinfunction "57_57") (pintype "bidirectional"))
    )
    (net (code "41") (name "N16_N") (class "Default")
      (node (ref "U$2") (pin "E14") (pinfunction "OUT46_P_E14") (pintype "output"))
      (node (ref "X-NORTH") (pin "64") (pinfunction "64_64") (pintype "bidirectional"))
    )
    (net (code "42") (name "N16_P") (class "Default")
      (node (ref "U$2") (pin "E13") (pinfunction "OUT46_N_E13") (pintype "output"))
      (node (ref "X-NORTH") (pin "62") (pinfunction "62_62") (pintype "bidirectional"))
    )
    (net (code "43") (name "N17_N") (class "Default")
      (node (ref "U$2") (pin "G15") (pinfunction "OUT47_P_G15") (pintype "output"))
      (node (ref "X-NORTH") (pin "65") (pinfunction "65_65") (pintype "bidirectional"))
    )
    (net (code "44") (name "N17_P") (class "Default")
      (node (ref "U$2") (pin "G14") (pinfunction "OUT47_N_G14") (pintype "output"))
      (node (ref "X-NORTH") (pin "63") (pinfunction "63_63") (pintype "bidirectional"))
    )
    (net (code "45") (name "N18_N") (class "Default")
      (node (ref "U$2") (pin "F15") (pinfunction "OUT48_P_F15") (pintype "output"))
      (node (ref "X-NORTH") (pin "70") (pinfunction "70_70") (pintype "bidirectional"))
    )
    (net (code "46") (name "N18_P") (class "Default")
      (node (ref "U$2") (pin "F14") (pinfunction "OUT48_N_F14") (pintype "output"))
      (node (ref "X-NORTH") (pin "68") (pinfunction "68_68") (pintype "bidirectional"))
    )
    (net (code "47") (name "N19_N") (class "Default")
      (node (ref "U$2") (pin "G17") (pinfunction "OUT50_P_G17") (pintype "output"))
      (node (ref "X-NORTH") (pin "71") (pinfunction "71_71") (pintype "bidirectional"))
    )
    (net (code "48") (name "N19_P") (class "Default")
      (node (ref "U$2") (pin "G16") (pinfunction "OUT50_N_G16") (pintype "output"))
      (node (ref "X-NORTH") (pin "69") (pinfunction "69_69") (pintype "bidirectional"))
    )
    (net (code "49") (name "N20_N") (class "Default")
      (node (ref "U$2") (pin "F17") (pinfunction "OUT49_P_F17") (pintype "output"))
      (node (ref "X-NORTH") (pin "76") (pinfunction "76_76") (pintype "bidirectional"))
    )
    (net (code "50") (name "N20_P") (class "Default")
      (node (ref "U$2") (pin "F16") (pinfunction "OUT49_N_F16") (pintype "output"))
      (node (ref "X-NORTH") (pin "74") (pinfunction "74_74") (pintype "bidirectional"))
    )
    (net (code "51") (name "N21_N") (class "Default")
      (node (ref "U$2") (pin "H18") (pinfunction "OUT52_P_H18") (pintype "output"))
      (node (ref "X-NORTH") (pin "77") (pinfunction "77_77") (pintype "bidirectional"))
    )
    (net (code "52") (name "N21_P") (class "Default")
      (node (ref "U$2") (pin "H17") (pinfunction "OUT52_N_H17") (pintype "output"))
      (node (ref "X-NORTH") (pin "75") (pinfunction "75_75") (pintype "bidirectional"))
    )
    (net (code "53") (name "N22_N") (class "Default")
      (node (ref "U$2") (pin "E18") (pinfunction "OUT51_P_E18") (pintype "output"))
      (node (ref "X-NORTH") (pin "82") (pinfunction "82_82") (pintype "bidirectional"))
    )
    (net (code "54") (name "N22_P") (class "Default")
      (node (ref "U$2") (pin "E17") (pinfunction "OUT51_N_E17") (pintype "output"))
      (node (ref "X-NORTH") (pin "80") (pinfunction "80_80") (pintype "bidirectional"))
    )
    (net (code "55") (name "N23_N") (class "Default")
      (node (ref "U$2") (pin "G19") (pinfunction "OUT54_P_G19") (pintype "output"))
      (node (ref "X-NORTH") (pin "83") (pinfunction "83_83") (pintype "bidirectional"))
    )
    (net (code "56") (name "N23_P") (class "Default")
      (node (ref "U$2") (pin "G18") (pinfunction "OUT54_N_G18") (pintype "output"))
      (node (ref "X-NORTH") (pin "81") (pinfunction "81_81") (pintype "bidirectional"))
    )
    (net (code "57") (name "N24_N") (class "Default")
      (node (ref "U$2") (pin "F19") (pinfunction "OUT53_P_F19") (pintype "output"))
      (node (ref "X-NORTH") (pin "88") (pinfunction "88_88") (pintype "bidirectional"))
    )
    (net (code "58") (name "N24_P") (class "Default")
      (node (ref "U$2") (pin "F18") (pinfunction "OUT53_N_F18") (pintype "output"))
      (node (ref "X-NORTH") (pin "86") (pinfunction "86_86") (pintype "bidirectional"))
    )
    (net (code "59") (name "N25_N") (class "Default")
      (node (ref "U$2") (pin "H20") (pinfunction "OUT56_P_H20") (pintype "output"))
      (node (ref "X-NORTH") (pin "89") (pinfunction "89_89") (pintype "bidirectional"))
    )
    (net (code "60") (name "N25_P") (class "Default")
      (node (ref "U$2") (pin "H19") (pinfunction "OUT56_N_H19") (pintype "output"))
      (node (ref "X-NORTH") (pin "87") (pinfunction "87_87") (pintype "bidirectional"))
    )
    (net (code "61") (name "N26_N") (class "Default")
      (node (ref "U$2") (pin "E20") (pinfunction "OUT55_P_E20") (pintype "output"))
      (node (ref "X-NORTH") (pin "94") (pinfunction "94_94") (pintype "bidirectional"))
    )
    (net (code "62") (name "N26_P") (class "Default")
      (node (ref "U$2") (pin "E19") (pinfunction "OUT55_N_E19") (pintype "output"))
      (node (ref "X-NORTH") (pin "92") (pinfunction "92_92") (pintype "bidirectional"))
    )
    (net (code "63") (name "N27_N") (class "Default")
      (node (ref "U$2") (pin "G21") (pinfunction "OUT58_P_G21") (pintype "output"))
      (node (ref "X-NORTH") (pin "95") (pinfunction "95_95") (pintype "bidirectional"))
    )
    (net (code "64") (name "N27_P") (class "Default")
      (node (ref "U$2") (pin "G20") (pinfunction "OUT58_N_G20") (pintype "output"))
      (node (ref "X-NORTH") (pin "93") (pinfunction "93_93") (pintype "bidirectional"))
    )
    (net (code "65") (name "N28_N") (class "Default")
      (node (ref "U$2") (pin "F21") (pinfunction "OUT57_P_F21") (pintype "output"))
      (node (ref "X-NORTH") (pin "100") (pinfunction "100_100") (pintype "bidirectional"))
    )
    (net (code "66") (name "N28_P") (class "Default")
      (node (ref "U$2") (pin "F20") (pinfunction "OUT57_N_F20") (pintype "output"))
      (node (ref "X-NORTH") (pin "98") (pinfunction "98_98") (pintype "bidirectional"))
    )
    (net (code "67") (name "N29_N") (class "Default")
      (node (ref "U$2") (pin "G23") (pinfunction "OUT61_P_G23") (pintype "output"))
      (node (ref "X-NORTH") (pin "101") (pinfunction "101_101") (pintype "bidirectional"))
    )
    (net (code "68") (name "N29_P") (class "Default")
      (node (ref "U$2") (pin "G22") (pinfunction "OUT61_N_G22") (pintype "output"))
      (node (ref "X-NORTH") (pin "99") (pinfunction "99_99") (pintype "bidirectional"))
    )
    (net (code "69") (name "N30_N") (class "Default")
      (node (ref "U$2") (pin "E22") (pinfunction "OUT59_P_E22") (pintype "output"))
      (node (ref "X-NORTH") (pin "106") (pinfunction "106_106") (pintype "bidirectional"))
    )
    (net (code "70") (name "N30_P") (class "Default")
      (node (ref "U$2") (pin "E21") (pinfunction "OUT59_N_E21") (pintype "output"))
      (node (ref "X-NORTH") (pin "104") (pinfunction "104_104") (pintype "bidirectional"))
    )
    (net (code "71") (name "N31_N") (class "Default")
      (node (ref "U$2") (pin "H24") (pinfunction "OUT63_P_H24") (pintype "output"))
      (node (ref "X-NORTH") (pin "107") (pinfunction "107_107") (pintype "bidirectional"))
    )
    (net (code "72") (name "N31_P") (class "Default")
      (node (ref "U$2") (pin "H23") (pinfunction "OUT63_N_H23") (pintype "output"))
      (node (ref "X-NORTH") (pin "105") (pinfunction "105_105") (pintype "bidirectional"))
    )
    (net (code "73") (name "N32_N") (class "Default")
      (node (ref "U$2") (pin "F23") (pinfunction "OUT60_P_F23") (pintype "output"))
      (node (ref "X-NORTH") (pin "112") (pinfunction "112_112") (pintype "bidirectional"))
    )
    (net (code "74") (name "N32_P") (class "Default")
      (node (ref "U$2") (pin "F22") (pinfunction "OUT60_N_F22") (pintype "output"))
      (node (ref "X-NORTH") (pin "110") (pinfunction "110_110") (pintype "bidirectional"))
    )
    (net (code "75") (name "N33_N") (class "Default")
      (node (ref "U$2") (pin "G25") (pinfunction "OUT64_P_G25") (pintype "output"))
      (node (ref "X-NORTH") (pin "113") (pinfunction "113_113") (pintype "bidirectional"))
    )
    (net (code "76") (name "N33_P") (class "Default")
      (node (ref "U$2") (pin "G24") (pinfunction "OUT64_N_G24") (pintype "output"))
      (node (ref "X-NORTH") (pin "111") (pinfunction "111_111") (pintype "bidirectional"))
    )
    (net (code "77") (name "N34_N") (class "Default")
      (node (ref "U$2") (pin "E24") (pinfunction "OUT62_P_E24") (pintype "output"))
      (node (ref "X-NORTH") (pin "118") (pinfunction "118_118") (pintype "bidirectional"))
    )
    (net (code "78") (name "N34_P") (class "Default")
      (node (ref "U$2") (pin "E23") (pinfunction "OUT62_N_E23") (pintype "output"))
      (node (ref "X-NORTH") (pin "116") (pinfunction "116_116") (pintype "bidirectional"))
    )
    (net (code "79") (name "N35_N") (class "Default")
      (node (ref "U6") (pin "4") (pinfunction "A4_4") (pintype "bidirectional"))
      (node (ref "X-NORTH") (pin "119") (pinfunction "119_119") (pintype "bidirectional"))
    )
    (net (code "80") (name "N35_P") (class "Default")
      (node (ref "U6") (pin "3") (pinfunction "A3_3") (pintype "bidirectional"))
      (node (ref "X-NORTH") (pin "117") (pinfunction "117_117") (pintype "bidirectional"))
    )
    (net (code "81") (name "N36_N") (class "Default")
      (node (ref "X-NORTH") (pin "124") (pinfunction "124_124") (pintype "bidirectional"))
    )
    (net (code "82") (name "N36_P") (class "Default")
      (node (ref "X-NORTH") (pin "122") (pinfunction "122_122") (pintype "bidirectional"))
    )
    (net (code "83") (name "N37_N") (class "Default")
      (node (ref "U5") (pin "3") (pinfunction "A3_3") (pintype "bidirectional"))
      (node (ref "X-NORTH") (pin "125") (pinfunction "125_125") (pintype "bidirectional"))
    )
    (net (code "84") (name "N37_P") (class "Default")
      (node (ref "U5") (pin "4") (pinfunction "A4_4") (pintype "bidirectional"))
      (node (ref "X-NORTH") (pin "123") (pinfunction "123_123") (pintype "bidirectional"))
    )
    (net (code "85") (name "N38_N") (class "Default")
      (node (ref "U6") (pin "2") (pinfunction "A2_2") (pintype "bidirectional"))
      (node (ref "X-NORTH") (pin "130") (pinfunction "130_130") (pintype "bidirectional"))
    )
    (net (code "86") (name "N38_P") (class "Default")
      (node (ref "U6") (pin "1") (pinfunction "A1_1") (pintype "bidirectional"))
      (node (ref "X-NORTH") (pin "128") (pinfunction "128_128") (pintype "bidirectional"))
    )
    (net (code "87") (name "N39_N") (class "Default")
      (node (ref "U5") (pin "1") (pinfunction "A1_1") (pintype "bidirectional"))
      (node (ref "X-NORTH") (pin "131") (pinfunction "131_131") (pintype "bidirectional"))
    )
    (net (code "88") (name "N39_P") (class "Default")
      (node (ref "U5") (pin "2") (pinfunction "A2_2") (pintype "bidirectional"))
      (node (ref "X-NORTH") (pin "129") (pinfunction "129_129") (pintype "bidirectional"))
    )
    (net (code "89") (name "N_CHK_V") (class "Default")
      (node (ref "C2") (pin "1") (pinfunction "1_1") (pintype "passive"))
      (node (ref "C3") (pin "1") (pinfunction "1_1") (pintype "passive"))
      (node (ref "C4") (pin "1") (pinfunction "1_1") (pintype "passive"))
      (node (ref "R19") (pin "1") (pinfunction "1_1") (pintype "passive"))
      (node (ref "TP1") (pin "TP") (pinfunction "TP_TP") (pintype "input"))
      (node (ref "UNE") (pin "8") (pinfunction "VDD_8") (pintype "power_in"))
      (node (ref "UNN") (pin "8") (pinfunction "VDD_8") (pintype "power_in"))
      (node (ref "UNW") (pin "8") (pinfunction "VDD_8") (pintype "power_in"))
      (node (ref "X-NORTH") (pin "10") (pinfunction "10_10") (pintype "bidirectional"))
      (node (ref "X-NORTH") (pin "8") (pinfunction "8_8") (pintype "bidirectional"))
    )
    (net (code "90") (name "N_I2C_V") (class "Default")
      (node (ref "C1") (pin "1") (pinfunction "1_1") (pintype "passive"))
      (node (ref "R1X") (pin "1") (pinfunction "1_1") (pintype "passive"))
      (node (ref "UEP") (pin "8") (pinfunction "VCC_8") (pintype "power_in"))
      (node (ref "X-NORTH") (pin "135") (pinfunction "135_135") (pintype "bidirectional"))
      (node (ref "X-NORTH") (pin "137") (pinfunction "137_137") (pintype "bidirectional"))
    )
    (net (code "91") (name "N_REF") (class "Default")
      (node (ref "R19") (pin "2") (pinfunction "2_2") (pintype "passive"))
      (node (ref "TP2") (pin "TP") (pinfunction "TP_TP") (pintype "input"))
      (node (ref "U1") (pin "3") (pinfunction "CATHODE_3") (pintype "output"))
      (node (ref "U1") (pin "4") (pinfunction "REF_4") (pintype "input"))
      (node (ref "UNE") (pin "2") (pinfunction "VINA-_2") (pintype "input"))
      (node (ref "UNE") (pin "5") (pinfunction "VINB+_5") (pintype "input"))
      (node (ref "UNN") (pin "2") (pinfunction "VINA-_2") (pintype "input"))
      (node (ref "UNN") (pin "5") (pinfunction "VINB+_5") (pintype "input"))
      (node (ref "UNW") (pin "2") (pinfunction "VINA-_2") (pintype "input"))
      (node (ref "UNW") (pin "5") (pinfunction "VINB+_5") (pintype "input"))
    )
    (net (code "92") (name "N_SCK") (class "Default")
      (node (ref "U4") (pin "15") (pinfunction "1B1_15") (pintype "output"))
      (node (ref "X-NORTH") (pin "144") (pinfunction "144_144") (pintype "bidirectional"))
    )
    (net (code "93") (name "N_SCL") (class "Default")
      (node (ref "UEP") (pin "6") (pinfunction "SCL_6") (pintype "input"))
      (node (ref "X-NORTH") (pin "143") (pinfunction "143_143") (pintype "bidirectional"))
    )
    (net (code "94") (name "N_SDA") (class "Default")
      (node (ref "UEP") (pin "5") (pinfunction "SDA_5") (pintype "bidirectional"))
      (node (ref "X-NORTH") (pin "141") (pinfunction "141_141") (pintype "bidirectional"))
    )
    (net (code "95") (name "N_SDI") (class "Default")
      (node (ref "U4") (pin "13") (pinfunction "2B1_13") (pintype "output"))
      (node (ref "X-NORTH") (pin "140") (pinfunction "140_140") (pintype "bidirectional"))
    )
    (net (code "96") (name "N_SDO") (class "Default")
      (node (ref "U4") (pin "14") (pinfunction "1B2_14") (pintype "output"))
      (node (ref "X-NORTH") (pin "142") (pinfunction "142_142") (pintype "bidirectional"))
    )
    (net (code "97") (name "N_SPI_V") (class "Default")
      (node (ref "C71") (pin "1") (pinfunction "1_1") (pintype "passive"))
      (node (ref "U4") (pin "2") (pinfunction "VCCB_2") (pintype "power_in"))
      (node (ref "X-NORTH") (pin "134") (pinfunction "134_134") (pintype "bidirectional"))
      (node (ref "X-NORTH") (pin "136") (pinfunction "136_136") (pintype "bidirectional"))
    )
    (net (code "98") (name "N_VE") (class "Default")
      (node (ref "C50") (pin "1") (pinfunction "1_1") (pintype "passive"))
      (node (ref "C51") (pin "1") (pinfunction "1_1") (pintype "passive"))
      (node (ref "C52") (pin "1") (pinfunction "1_1") (pintype "passive"))
      (node (ref "C53") (pin "1") (pinfunction "1_1") (pintype "passive"))
      (node (ref "C54") (pin "1") (pinfunction "1_1") (pintype "passive"))
      (node (ref "C55") (pin "1") (pinfunction "1_1") (pintype "passive"))
      (node (ref "C56") (pin "1") (pinfunction "1_1") (pintype "passive"))
      (node (ref "C67") (pin "1") (pinfunction "1_1") (pintype "passive"))
      (node (ref "C69") (pin "1") (pinfunction "1_1") (pintype "passive"))
      (node (ref "C75") (pin "1") (pinfunction "1_1") (pintype "passive"))
      (node (ref "C76") (pin "1") (pinfunction "1_1") (pintype "passive"))
      (node (ref "C77") (pin "1") (pinfunction "1_1") (pintype "passive"))
      (node (ref "C84") (pin "1") (pinfunction "1_1") (pintype "passive"))
      (node (ref "C85") (pin "1") (pinfunction "1_1") (pintype "passive"))
      (node (ref "C86") (pin "1") (pinfunction "1_1") (pintype "passive"))
      (node (ref "TP7") (pin "TP") (pinfunction "TP_TP") (pintype "input"))
      (node (ref "U$2") (pin "C26") (pinfunction "VDD33_C26") (pintype "power_in"))
      (node (ref "U$2") (pin "C27") (pinfunction "VDD33_C27") (pintype "power_in"))
      (node (ref "U$2") (pin "D26") (pinfunction "VDD33_D26") (pintype "power_in"))
      (node (ref "U$2") (pin "D3") (pinfunction "VDD33_D3") (pintype "power_in"))
      (node (ref "U$2") (pin "E26") (pinfunction "VDD33_E26") (pintype "power_in"))
      (node (ref "U$2") (pin "F26") (pinfunction "VDD33_F26") (pintype "power_in"))
      (node (ref "U$2") (pin "F5") (pinfunction "VDD33_F5") (pintype "power_in"))
      (node (ref "U4") (pin "3") (pinfunction "VCCA_3") (pintype "power_in"))
      (node (ref "U4") (pin "5") (pinfunction "2DIR_5") (pintype "input"))
      (node (ref "U5") (pin "13") (pinfunction "VCCB_13") (pintype "power_in"))
      (node (ref "U6") (pin "13") (pinfunction "VCCB_13") (pintype "power_in"))
      (node (ref "X-NORTH") (pin "103") (pinfunction "103_103") (pintype "bidirectional"))
      (node (ref "X-NORTH") (pin "109") (pinfunction "109_109") (pintype "bidirectional"))
      (node (ref "X-NORTH") (pin "115") (pinfunction "115_115") (pintype "bidirectional"))
      (node (ref "X-NORTH") (pin "121") (pinfunction "121_121") (pintype "bidirectional"))
      (node (ref "X-NORTH") (pin "127") (pinfunction "127_127") (pintype "bidirectional"))
      (node (ref "X-NORTH") (pin "133") (pinfunction "133_133") (pintype "bidirectional"))
    )
    (net (code "99") (name "N_VE_CV") (class "Default")
      (node (ref "C10") (pin "1") (pinfunction "1_1") (pintype "passive"))
      (node (ref "R7") (pin "1") (pinfunction "1_1") (pintype "passive"))
      (node (ref "X-NORTH") (pin "6") (pinfunction "6_6") (pintype "bidirectional"))
    )
    (net (code "100") (name "N_VE_OV") (class "Default")
      (node (ref "UNE") (pin "7") (pinfunction "OUTB_7") (pintype "output"))
      (node (ref "X-NORTH") (pin "5") (pinfunction "5_5") (pintype "bidirectional"))
    )
    (net (code "101") (name "N_VE_UV") (class "Default")
      (node (ref "UNE") (pin "1") (pinfunction "OUTA_1") (pintype "output"))
      (node (ref "X-NORTH") (pin "11") (pinfunction "11_11") (pintype "bidirectional"))
    )
    (net (code "102") (name "N_VN") (class "Default")
      (node (ref "C31") (pin "1") (pinfunction "1_1") (pintype "passive"))
      (node (ref "C32") (pin "1") (pinfunction "1_1") (pintype "passive"))
      (node (ref "C33") (pin "1") (pinfunction "1_1") (pintype "passive"))
      (node (ref "C34") (pin "1") (pinfunction "1_1") (pintype "passive"))
      (node (ref "C35") (pin "1") (pinfunction "1_1") (pintype "passive"))
      (node (ref "C36") (pin "1") (pinfunction "1_1") (pintype "passive"))
      (node (ref "C37") (pin "1") (pinfunction "1_1") (pintype "passive"))
      (node (ref "C38") (pin "1") (pinfunction "1_1") (pintype "passive"))
      (node (ref "C39") (pin "1") (pinfunction "1_1") (pintype "passive"))
      (node (ref "C40") (pin "1") (pinfunction "1_1") (pintype "passive"))
      (node (ref "C41") (pin "1") (pinfunction "1_1") (pintype "passive"))
      (node (ref "C42") (pin "1") (pinfunction "1_1") (pintype "passive"))
      (node (ref "C43") (pin "1") (pinfunction "1_1") (pintype "passive"))
      (node (ref "C44") (pin "1") (pinfunction "1_1") (pintype "passive"))
      (node (ref "C68") (pin "1") (pinfunction "1_1") (pintype "passive"))
      (node (ref "C70") (pin "1") (pinfunction "1_1") (pintype "passive"))
      (node (ref "C78") (pin "1") (pinfunction "1_1") (pintype "passive"))
      (node (ref "C79") (pin "1") (pinfunction "1_1") (pintype "passive"))
      (node (ref "C80") (pin "1") (pinfunction "1_1") (pintype "passive"))
      (node (ref "C87") (pin "1") (pinfunction "1_1") (pintype "passive"))
      (node (ref "C88") (pin "1") (pinfunction "1_1") (pintype "passive"))
      (node (ref "C89") (pin "1") (pinfunction "1_1") (pintype "passive"))
      (node (ref "TP5") (pin "TP") (pinfunction "TP_TP") (pintype "input"))
      (node (ref "U$2") (pin "A10") (pinfunction "VDD18_A10") (pintype "power_in"))
      (node (ref "U$2") (pin "A15") (pinfunction "VDD18_A15") (pintype "power_in"))
      (node (ref "U$2") (pin "A16") (pinfunction "VDD18_A16") (pintype "power_in"))
      (node (ref "U$2") (pin "A22") (pinfunction "VDD18_A22") (pintype "power_in"))
      (node (ref "U$2") (pin "A26") (pinfunction "VDD18_A26") (pintype "power_in"))
      (node (ref "U$2") (pin "A27") (pinfunction "VDD18_A27") (pintype "power_in"))
      (node (ref "U$2") (pin "B4") (pinfunction "VDD18_B4") (pintype "power_in"))
      (node (ref "U$2") (pin "E1") (pinfunction "VDD18_PLL_E1") (pintype "power_in"))
      (node (ref "U$2") (pin "H10") (pinfunction "VDD18_H10") (pintype "power_in"))
      (node (ref "U$2") (pin "H15") (pinfunction "VDD18_H15") (pintype "power_in"))
      (node (ref "U$2") (pin "H16") (pinfunction "VDD18_H16") (pintype "power_in"))
      (node (ref "U$2") (pin "H22") (pinfunction "VDD18_H22") (pintype "power_in"))
      (node (ref "U$2") (pin "H26") (pinfunction "VDD18_H26") (pintype "power_in"))
      (node (ref "U$2") (pin "H5") (pinfunction "VDD18_H5") (pintype "power_in"))
      (node (ref "U5") (pin "14") (pinfunction "VCCA_14") (pintype "power_in"))
      (node (ref "U5") (pin "15") (pinfunction "DIR1_15") (pintype "input"))
      (node (ref "U5") (pin "16") (pinfunction "DIR2_16") (pintype "input"))
      (node (ref "U5") (pin "5") (pinfunction "DIR3_5") (pintype "input"))
      (node (ref "U6") (pin "14") (pinfunction "VCCA_14") (pintype "power_in"))
      (node (ref "U6") (pin "16") (pinfunction "DIR2_16") (pintype "input"))
      (node (ref "X-NORTH") (pin "49") (pinfunction "49_49") (pintype "bidirectional"))
      (node (ref "X-NORTH") (pin "55") (pinfunction "55_55") (pintype "bidirectional"))
      (node (ref "X-NORTH") (pin "61") (pinfunction "61_61") (pintype "bidirectional"))
      (node (ref "X-NORTH") (pin "67") (pinfunction "67_67") (pintype "bidirectional"))
      (node (ref "X-NORTH") (pin "73") (pinfunction "73_73") (pintype "bidirectional"))
      (node (ref "X-NORTH") (pin "79") (pinfunction "79_79") (pintype "bidirectional"))
      (node (ref "X-NORTH") (pin "85") (pinfunction "85_85") (pintype "bidirectional"))
      (node (ref "X-NORTH") (pin "91") (pinfunction "91_91") (pintype "bidirectional"))
      (node (ref "X-NORTH") (pin "97") (pinfunction "97_97") (pintype "bidirectional"))
    )
    (net (code "103") (name "N_VN_CV") (class "Default")
      (node (ref "C9") (pin "1") (pinfunction "1_1") (pintype "passive"))
      (node (ref "R4") (pin "1") (pinfunction "1_1") (pintype "passive"))
      (node (ref "X-NORTH") (pin "4") (pinfunction "4_4") (pintype "bidirectional"))
    )
    (net (code "104") (name "N_VN_OV") (class "Default")
      (node (ref "UNN") (pin "7") (pinfunction "OUTB_7") (pintype "output"))
      (node (ref "X-NORTH") (pin "3") (pinfunction "3_3") (pintype "bidirectional"))
    )
    (net (code "105") (name "N_VN_UV") (class "Default")
      (node (ref "UNN") (pin "1") (pinfunction "OUTA_1") (pintype "output"))
      (node (ref "X-NORTH") (pin "9") (pinfunction "9_9") (pintype "bidirectional"))
    )
    (net (code "106") (name "N_VW") (class "Default")
      (node (ref "C57") (pin "1") (pinfunction "1_1") (pintype "passive"))
      (node (ref "C58") (pin "1") (pinfunction "1_1") (pintype "passive"))
      (node (ref "C59") (pin "1") (pinfunction "1_1") (pintype "passive"))
      (node (ref "TP8") (pin "TP") (pinfunction "TP_TP") (pintype "input"))
      (node (ref "U$2") (pin "E2") (pinfunction "VDD_RES_E2") (pintype "power_in"))
      (node (ref "U$2") (pin "G4") (pinfunction "VDD_RES_G4") (pintype "power_in"))
      (node (ref "X-NORTH") (pin "13") (pinfunction "13_13") (pintype "bidirectional"))
      (node (ref "X-NORTH") (pin "19") (pinfunction "19_19") (pintype "bidirectional"))
      (node (ref "X-NORTH") (pin "25") (pinfunction "25_25") (pintype "bidirectional"))
      (node (ref "X-NORTH") (pin "31") (pinfunction "31_31") (pintype "bidirectional"))
      (node (ref "X-NORTH") (pin "37") (pinfunction "37_37") (pintype "bidirectional"))
      (node (ref "X-NORTH") (pin "43") (pinfunction "43_43") (pintype "bidirectional"))
    )
    (net (code "107") (name "N_VW_CV") (class "Default")
      (node (ref "C8") (pin "1") (pinfunction "1_1") (pintype "passive"))
      (node (ref "R1") (pin "1") (pinfunction "1_1") (pintype "passive"))
      (node (ref "X-NORTH") (pin "2") (pinfunction "2_2") (pintype "bidirectional"))
    )
    (net (code "108") (name "N_VW_OV") (class "Default")
      (node (ref "UNW") (pin "7") (pinfunction "OUTB_7") (pintype "output"))
      (node (ref "X-NORTH") (pin "1") (pinfunction "1_1") (pintype "bidirectional"))
    )
    (net (code "109") (name "N_VW_UV") (class "Default")
      (node (ref "UNW") (pin "1") (pinfunction "OUTA_1") (pintype "output"))
      (node (ref "X-NORTH") (pin "7") (pinfunction "7_7") (pintype "bidirectional"))
    )
    (net (code "110") (name "Net-(U$2B-CMDN)") (class "Default")
      (node (ref "C119") (pin "1") (pinfunction "1_1") (pintype "passive"))
      (node (ref "U$2") (pin "F1") (pinfunction "CMDN_F1") (pintype "bidirectional"))
    )
    (net (code "111") (name "Net-(U$2B-CMDP)") (class "Default")
      (node (ref "C22") (pin "2") (pinfunction "2_2") (pintype "passive"))
      (node (ref "U$2") (pin "F2") (pinfunction "CMDP_F2") (pintype "bidirectional"))
    )
    (net (code "112") (name "Net-(U$2B-CMDP_COMP)") (class "Default")
      (node (ref "C28") (pin "2") (pinfunction "2_2") (pintype "passive"))
      (node (ref "U$2") (pin "H3") (pinfunction "CMDP_COMP_H3") (pintype "bidirectional"))
    )
    (net (code "113") (name "Net-(U$2B-CMDP_COMP_INV)") (class "Default")
      (node (ref "C27") (pin "2") (pinfunction "2_2") (pintype "passive"))
      (node (ref "U$2") (pin "F3") (pinfunction "CMDP_COMP_INV_F3") (pintype "bidirectional"))
    )
    (net (code "114") (name "Net-(U$2B-CMD_COLAMP)") (class "Default")
      (node (ref "C25") (pin "2") (pinfunction "2_2") (pintype "passive"))
      (node (ref "U$2") (pin "C6") (pinfunction "CMD_COLAMP_C6") (pintype "bidirectional"))
    )
    (net (code "115") (name "Net-(U$2B-CMD_COL_LOAD)") (class "Default")
      (node (ref "C23") (pin "2") (pinfunction "2_2") (pintype "passive"))
      (node (ref "U$2") (pin "B1") (pinfunction "CMD_COL_LOAD_B1") (pintype "bidirectional"))
    )
    (net (code "116") (name "Net-(U$2B-CMD_COL_PC)") (class "Default")
      (node (ref "C26") (pin "2") (pinfunction "2_2") (pintype "passive"))
      (node (ref "U$2") (pin "D1") (pinfunction "CMD_COL_PC_D1") (pintype "bidirectional"))
    )
    (net (code "117") (name "Net-(U$2B-CMD_LVDS)") (class "Default")
      (node (ref "C120") (pin "1") (pinfunction "1_1") (pintype "passive"))
      (node (ref "U$2") (pin "C1") (pinfunction "CMD_LVDS_C1") (pintype "bidirectional"))
    )
    (net (code "118") (name "Net-(U$2B-CMD_RAMP)") (class "Default")
      (node (ref "C24") (pin "2") (pinfunction "2_2") (pintype "passive"))
      (node (ref "U$2") (pin "B29") (pinfunction "CMD_RAMP_B29") (pintype "bidirectional"))
    )
    (net (code "119") (name "Net-(U$2B-VBGAP)") (class "Default")
      (node (ref "C122") (pin "1") (pinfunction "1_1") (pintype "passive"))
      (node (ref "U$2") (pin "C29") (pinfunction "VBGAP_C29") (pintype "bidirectional"))
    )
    (net (code "120") (name "Net-(U$2B-VCLAMP)") (class "Default")
      (node (ref "C121") (pin "1") (pinfunction "1_1") (pintype "passive"))
      (node (ref "U$2") (pin "D4") (pinfunction "VCLAMP_D4") (pintype "bidirectional"))
    )
    (net (code "121") (name "Net-(U$2B-VCLAMP_ADC)") (class "Default")
      (node (ref "C118") (pin "1") (pinfunction "1_1") (pintype "passive"))
      (node (ref "U$2") (pin "G2") (pinfunction "VCLAMP_ADC_G2") (pintype "bidirectional"))
    )
    (net (code "122") (name "Net-(U$2B-VPCH_H)") (class "Default")
      (node (ref "C123") (pin "1") (pinfunction "1_1") (pintype "passive"))
      (node (ref "U$2") (pin "C4") (pinfunction "VPCH_H_C4") (pintype "bidirectional"))
    )
    (net (code "123") (name "Net-(U$2B-VPCH_L)") (class "Default")
      (node (ref "C14") (pin "1") (pinfunction "1_1") (pintype "passive"))
      (node (ref "U$2") (pin "A4") (pinfunction "VPCH_L_A4") (pintype "bidirectional"))
    )
    (net (code "124") (name "Net-(U$2B-VREF)") (class "Default")
      (node (ref "C29") (pin "1") (pinfunction "1_1") (pintype "passive"))
      (node (ref "U$2") (pin "A3") (pinfunction "VREF_A3") (pintype "bidirectional"))
    )
    (net (code "125") (name "Net-(U$2B-VREF_ADC)") (class "Default")
      (node (ref "C30") (pin "1") (pinfunction "1_1") (pintype "passive"))
      (node (ref "U$2") (pin "B3") (pinfunction "VREF_ADC_B3") (pintype "bidirectional"))
    )
    (net (code "126") (name "Net-(U$2B-VRES_L)") (class "Default")
      (node (ref "C15") (pin "1") (pinfunction "1_1") (pintype "passive"))
      (node (ref "U$2") (pin "D5") (pinfunction "VRES_L_D5") (pintype "bidirectional"))
    )
    (net (code "127") (name "Net-(U$2B-VTF_LOW0)") (class "Default")
      (node (ref "C18") (pin "1") (pinfunction "1_1") (pintype "passive"))
      (node (ref "U$2") (pin "C5") (pinfunction "VTF_LOW0_C5") (pintype "bidirectional"))
    )
    (net (code "128") (name "Net-(U$2B-VTF_LOW1)") (class "Default")
      (node (ref "C19") (pin "1") (pinfunction "1_1") (pintype "passive"))
      (node (ref "U$2") (pin "D6") (pinfunction "VTF_LOW1_D6") (pintype "bidirectional"))
    )
    (net (code "129") (name "Net-(U$2B-VTF_LOW2)") (class "Default")
      (node (ref "C20") (pin "1") (pinfunction "1_1") (pintype "passive"))
      (node (ref "U$2") (pin "B30") (pinfunction "VTF_LOW2_B30") (pintype "bidirectional"))
    )
    (net (code "130") (name "Net-(U$2B-VTF_LOW3)") (class "Default")
      (node (ref "C21") (pin "1") (pinfunction "1_1") (pintype "passive"))
      (node (ref "U$2") (pin "C30") (pinfunction "VTF_LOW3_C30") (pintype "bidirectional"))
    )
    (net (code "131") (name "Net-(U$4-ADJ)") (class "Default")
      (node (ref "R21") (pin "1") (pinfunction "1_1") (pintype "passive"))
      (node (ref "R22") (pin "2") (pinfunction "2_2") (pintype "passive"))
      (node (ref "U$4") (pin "5") (pinfunction "ADJ_5") (pintype "input"))
    )
    (net (code "132") (name "Net-(UEP-WP)") (class "Default")
      (node (ref "R1X") (pin "2") (pinfunction "2_2") (pintype "passive"))
      (node (ref "R2X") (pin "1") (pinfunction "1_1") (pintype "passive"))
      (node (ref "UEP") (pin "7") (pinfunction "WP_7") (pintype "input"))
    )
    (net (code "133") (name "Net-(UNE-VINA+)") (class "Default")
      (node (ref "R7") (pin "2") (pinfunction "2_2") (pintype "passive"))
      (node (ref "R8") (pin "1") (pinfunction "1_1") (pintype "passive"))
      (node (ref "UNE") (pin "3") (pinfunction "VINA+_3") (pintype "input"))
    )
    (net (code "134") (name "Net-(UNE-VINB-)") (class "Default")
      (node (ref "R8") (pin "2") (pinfunction "2_2") (pintype "passive"))
      (node (ref "R9") (pin "1") (pinfunction "1_1") (pintype "passive"))
      (node (ref "UNE") (pin "6") (pinfunction "VINB-_6") (pintype "input"))
    )
    (net (code "135") (name "Net-(UNN-VINA+)") (class "Default")
      (node (ref "R4") (pin "2") (pinfunction "2_2") (pintype "passive"))
      (node (ref "R5") (pin "1") (pinfunction "1_1") (pintype "passive"))
      (node (ref "UNN") (pin "3") (pinfunction "VINA+_3") (pintype "input"))
    )
    (net (code "136") (name "Net-(UNN-VINB-)") (class "Default")
      (node (ref "R5") (pin "2") (pinfunction "2_2") (pintype "passive"))
      (node (ref "R6") (pin "1") (pinfunction "1_1") (pintype "passive"))
      (node (ref "UNN") (pin "6") (pinfunction "VINB-_6") (pintype "input"))
    )
    (net (code "137") (name "Net-(UNW-VINA+)") (class "Default")
      (node (ref "R1") (pin "2") (pinfunction "2_2") (pintype "passive"))
      (node (ref "R2") (pin "1") (pinfunction "1_1") (pintype "passive"))
      (node (ref "UNW") (pin "3") (pinfunction "VINA+_3") (pintype "input"))
    )
    (net (code "138") (name "Net-(UNW-VINB-)") (class "Default")
      (node (ref "R2") (pin "2") (pinfunction "2_2") (pintype "passive"))
      (node (ref "R3") (pin "1") (pinfunction "1_1") (pintype "passive"))
      (node (ref "UNW") (pin "6") (pinfunction "VINB-_6") (pintype "input"))
    )
    (net (code "139") (name "Net-(USE-VINA+)") (class "Default")
      (node (ref "R10") (pin "2") (pinfunction "2_2") (pintype "passive"))
      (node (ref "R11") (pin "1") (pinfunction "1_1") (pintype "passive"))
      (node (ref "USE") (pin "3") (pinfunction "VINA+_3") (pintype "input"))
    )
    (net (code "140") (name "Net-(USE-VINB-)") (class "Default")
      (node (ref "R11") (pin "2") (pinfunction "2_2") (pintype "passive"))
      (node (ref "R12") (pin "1") (pinfunction "1_1") (pintype "passive"))
      (node (ref "USE") (pin "6") (pinfunction "VINB-_6") (pintype "input"))
    )
    (net (code "141") (name "Net-(USS-VINA+)") (class "Default")
      (node (ref "R13") (pin "2") (pinfunction "2_2") (pintype "passive"))
      (node (ref "R14") (pin "1") (pinfunction "1_1") (pintype "passive"))
      (node (ref "USS") (pin "3") (pinfunction "VINA+_3") (pintype "input"))
    )
    (net (code "142") (name "Net-(USS-VINB-)") (class "Default")
      (node (ref "R14") (pin "2") (pinfunction "2_2") (pintype "passive"))
      (node (ref "R15") (pin "1") (pinfunction "1_1") (pintype "passive"))
      (node (ref "USS") (pin "6") (pinfunction "VINB-_6") (pintype "input"))
    )
    (net (code "143") (name "Net-(USW-VINA+)") (class "Default")
      (node (ref "R16") (pin "2") (pinfunction "2_2") (pintype "passive"))
      (node (ref "R17") (pin "1") (pinfunction "1_1") (pintype "passive"))
      (node (ref "USW") (pin "3") (pinfunction "VINA+_3") (pintype "input"))
    )
    (net (code "144") (name "Net-(USW-VINB-)") (class "Default")
      (node (ref "R17") (pin "2") (pinfunction "2_2") (pintype "passive"))
      (node (ref "R18") (pin "1") (pinfunction "1_1") (pintype "passive"))
      (node (ref "USW") (pin "6") (pinfunction "VINB-_6") (pintype "input"))
    )
    (net (code "145") (name "S00_N") (class "Default")
      (node (ref "X-SOUTH") (pin "16") (pinfunction "16_16") (pintype "bidirectional"))
    )
    (net (code "146") (name "S00_P") (class "Default")
      (node (ref "X-SOUTH") (pin "14") (pinfunction "14_14") (pintype "bidirectional"))
    )
    (net (code "147") (name "S01_N") (class "Default")
      (node (ref "X-SOUTH") (pin "17") (pinfunction "17_17") (pintype "bidirectional"))
    )
    (net (code "148") (name "S01_P") (class "Default")
      (node (ref "X-SOUTH") (pin "15") (pinfunction "15_15") (pintype "bidirectional"))
    )
    (net (code "149") (name "S02_N") (class "Default")
      (node (ref "X-SOUTH") (pin "22") (pinfunction "22_22") (pintype "bidirectional"))
    )
    (net (code "150") (name "S02_P") (class "Default")
      (node (ref "X-SOUTH") (pin "20") (pinfunction "20_20") (pintype "bidirectional"))
    )
    (net (code "151") (name "S03_N") (class "Default")
      (node (ref "X-SOUTH") (pin "23") (pinfunction "23_23") (pintype "bidirectional"))
    )
    (net (code "152") (name "S03_P") (class "Default")
      (node (ref "X-SOUTH") (pin "21") (pinfunction "21_21") (pintype "bidirectional"))
    )
    (net (code "153") (name "S04_N") (class "Default")
      (node (ref "U$2") (pin "C24") (pinfunction "OUT32_N_C24") (pintype "output"))
      (node (ref "X-SOUTH") (pin "28") (pinfunction "28_28") (pintype "bidirectional"))
    )
    (net (code "154") (name "S04_P") (class "Default")
      (node (ref "U$2") (pin "C25") (pinfunction "OUT32_P_C25") (pintype "output"))
      (node (ref "X-SOUTH") (pin "26") (pinfunction "26_26") (pintype "bidirectional"))
    )
    (net (code "155") (name "S05_N") (class "Default")
      (node (ref "X-SOUTH") (pin "29") (pinfunction "29_29") (pintype "bidirectional"))
    )
    (net (code "156") (name "S05_P") (class "Default")
      (node (ref "X-SOUTH") (pin "27") (pinfunction "27_27") (pintype "bidirectional"))
    )
    (net (code "157") (name "S06_N") (class "Default")
      (node (ref "U$2") (pin "D23") (pinfunction "OUT30_N_D23") (pintype "output"))
      (node (ref "X-SOUTH") (pin "34") (pinfunction "34_34") (pintype "bidirectional"))
    )
    (net (code "158") (name "S06_P") (class "Default")
      (node (ref "U$2") (pin "D24") (pinfunction "OUT30_P_D24") (pintype "output"))
      (node (ref "X-SOUTH") (pin "32") (pinfunction "32_32") (pintype "bidirectional"))
    )
    (net (code "159") (name "S07_N") (class "Default")
      (node (ref "U$2") (pin "B24") (pinfunction "OUT31_N_B24") (pintype "output"))
      (node (ref "X-SOUTH") (pin "35") (pinfunction "35_35") (pintype "bidirectional"))
    )
    (net (code "160") (name "S07_P") (class "Default")
      (node (ref "U$2") (pin "B25") (pinfunction "OUT31_P_B25") (pintype "output"))
      (node (ref "X-SOUTH") (pin "33") (pinfunction "33_33") (pintype "bidirectional"))
    )
    (net (code "161") (name "S08_N") (class "Default")
      (node (ref "U$2") (pin "D21") (pinfunction "OUT27_N_D21") (pintype "output"))
      (node (ref "X-SOUTH") (pin "40") (pinfunction "40_40") (pintype "bidirectional"))
    )
    (net (code "162") (name "S08_P") (class "Default")
      (node (ref "U$2") (pin "D22") (pinfunction "OUT27_P_D22") (pintype "output"))
      (node (ref "X-SOUTH") (pin "38") (pinfunction "38_38") (pintype "bidirectional"))
    )
    (net (code "163") (name "S09_N") (class "Default")
      (node (ref "U$2") (pin "A23") (pinfunction "OUT29_N_A23") (pintype "output"))
      (node (ref "X-SOUTH") (pin "41") (pinfunction "41_41") (pintype "bidirectional"))
    )
    (net (code "164") (name "S09_P") (class "Default")
      (node (ref "U$2") (pin "A24") (pinfunction "OUT29_P_A24") (pintype "output"))
      (node (ref "X-SOUTH") (pin "39") (pinfunction "39_39") (pintype "bidirectional"))
    )
    (net (code "165") (name "S10_N") (class "Default")
      (node (ref "U$2") (pin "C21") (pinfunction "OUT28_N_C21") (pintype "output"))
      (node (ref "X-SOUTH") (pin "46") (pinfunction "46_46") (pintype "bidirectional"))
    )
    (net (code "166") (name "S10_P") (class "Default")
      (node (ref "U$2") (pin "C22") (pinfunction "OUT28_P_C22") (pintype "output"))
      (node (ref "X-SOUTH") (pin "44") (pinfunction "44_44") (pintype "bidirectional"))
    )
    (net (code "167") (name "S11_N") (class "Default")
      (node (ref "U$2") (pin "B20") (pinfunction "OUT26_N_B20") (pintype "output"))
      (node (ref "X-SOUTH") (pin "47") (pinfunction "47_47") (pintype "bidirectional"))
    )
    (net (code "168") (name "S11_P") (class "Default")
      (node (ref "U$2") (pin "B21") (pinfunction "OUT26_P_B21") (pintype "output"))
      (node (ref "X-SOUTH") (pin "45") (pinfunction "45_45") (pintype "bidirectional"))
    )
    (net (code "169") (name "S12_N") (class "Default")
      (node (ref "U$2") (pin "D19") (pinfunction "OUT24_N_D19") (pintype "output"))
      (node (ref "X-SOUTH") (pin "52") (pinfunction "52_52") (pintype "bidirectional"))
    )
    (net (code "170") (name "S12_P") (class "Default")
      (node (ref "U$2") (pin "D20") (pinfunction "OUT24_P_D20") (pintype "output"))
      (node (ref "X-SOUTH") (pin "50") (pinfunction "50_50") (pintype "bidirectional"))
    )
    (net (code "171") (name "S13_N") (class "Default")
      (node (ref "U$2") (pin "A19") (pinfunction "OUT23_N_A19") (pintype "output"))
      (node (ref "X-SOUTH") (pin "53") (pinfunction "53_53") (pintype "bidirectional"))
    )
    (net (code "172") (name "S13_P") (class "Default")
      (node (ref "U$2") (pin "A20") (pinfunction "OUT23_P_A20") (pintype "output"))
      (node (ref "X-SOUTH") (pin "51") (pinfunction "51_51") (pintype "bidirectional"))
    )
    (net (code "173") (name "S14_N") (class "Default")
      (node (ref "U$2") (pin "C19") (pinfunction "OUT25_N_C19") (pintype "output"))
      (node (ref "X-SOUTH") (pin "58") (pinfunction "58_58") (pintype "bidirectional"))
    )
    (net (code "174") (name "S14_P") (class "Default")
      (node (ref "U$2") (pin "C20") (pinfunction "OUT25_P_C20") (pintype "output"))
      (node (ref "X-SOUTH") (pin "56") (pinfunction "56_56") (pintype "bidirectional"))
    )
    (net (code "175") (name "S15_N") (class "Default")
      (node (ref "U$2") (pin "B18") (pinfunction "OUT22_N_B18") (pintype "output"))
      (node (ref "X-SOUTH") (pin "59") (pinfunction "59_59") (pintype "bidirectional"))
    )
    (net (code "176") (name "S15_P") (class "Default")
      (node (ref "U$2") (pin "B19") (pinfunction "OUT22_P_B19") (pintype "output"))
      (node (ref "X-SOUTH") (pin "57") (pinfunction "57_57") (pintype "bidirectional"))
    )
    (net (code "177") (name "S16_N") (class "Default")
      (node (ref "U$2") (pin "C17") (pinfunction "OUT21_N_C17") (pintype "output"))
      (node (ref "X-SOUTH") (pin "64") (pinfunction "64_64") (pintype "bidirectional"))
    )
    (net (code "178") (name "S16_P") (class "Default")
      (node (ref "U$2") (pin "C18") (pinfunction "OUT21_P_C18") (pintype "output"))
      (node (ref "X-SOUTH") (pin "62") (pinfunction "62_62") (pintype "bidirectional"))
    )
    (net (code "179") (name "S17_N") (class "Default")
      (node (ref "U$2") (pin "A17") (pinfunction "OUT19_N_A17") (pintype "output"))
      (node (ref "X-SOUTH") (pin "65") (pinfunction "65_65") (pintype "bidirectional"))
    )
    (net (code "180") (name "S17_P") (class "Default")
      (node (ref "U$2") (pin "A18") (pinfunction "OUT19_P_A18") (pintype "output"))
      (node (ref "X-SOUTH") (pin "63") (pinfunction "63_63") (pintype "bidirectional"))
    )
    (net (code "181") (name "S18_N") (class "Default")
      (node (ref "U$2") (pin "D17") (pinfunction "OUT20_N_D17") (pintype "output"))
      (node (ref "X-SOUTH") (pin "70") (pinfunction "70_70") (pintype "bidirectional"))
    )
    (net (code "182") (name "S18_P") (class "Default")
      (node (ref "U$2") (pin "D18") (pinfunction "OUT20_P_D18") (pintype "output"))
      (node (ref "X-SOUTH") (pin "68") (pinfunction "68_68") (pintype "bidirectional"))
    )
    (net (code "183") (name "S19_N") (class "Default")
      (node (ref "U$2") (pin "B16") (pinfunction "OUT18_N_B16") (pintype "output"))
      (node (ref "X-SOUTH") (pin "71") (pinfunction "71_71") (pintype "bidirectional"))
    )
    (net (code "184") (name "S19_P") (class "Default")
      (node (ref "U$2") (pin "B17") (pinfunction "OUT18_P_B17") (pintype "output"))
      (node (ref "X-SOUTH") (pin "69") (pinfunction "69_69") (pintype "bidirectional"))
    )
    (net (code "185") (name "S20_N") (class "Default")
      (node (ref "U$2") (pin "D15") (pinfunction "OUT17_N_D15") (pintype "output"))
      (node (ref "X-SOUTH") (pin "76") (pinfunction "76_76") (pintype "bidirectional"))
    )
    (net (code "186") (name "S20_P") (class "Default")
      (node (ref "U$2") (pin "D16") (pinfunction "OUT17_P_D16") (pintype "output"))
      (node (ref "X-SOUTH") (pin "74") (pinfunction "74_74") (pintype "bidirectional"))
    )
    (net (code "187") (name "S21_N") (class "Default")
      (node (ref "U$2") (pin "B14") (pinfunction "OUT16_N_B14") (pintype "output"))
      (node (ref "X-SOUTH") (pin "77") (pinfunction "77_77") (pintype "bidirectional"))
    )
    (net (code "188") (name "S21_P") (class "Default")
      (node (ref "U$2") (pin "B15") (pinfunction "OUT16_P_B15") (pintype "output"))
      (node (ref "X-SOUTH") (pin "75") (pinfunction "75_75") (pintype "bidirectional"))
    )
    (net (code "189") (name "S22_N") (class "Default")
      (node (ref "U$2") (pin "D13") (pinfunction "OUT15_N_D13") (pintype "output"))
      (node (ref "X-SOUTH") (pin "82") (pinfunction "82_82") (pintype "bidirectional"))
    )
    (net (code "190") (name "S22_P") (class "Default")
      (node (ref "U$2") (pin "D14") (pinfunction "OUT15_P_D14") (pintype "output"))
      (node (ref "X-SOUTH") (pin "80") (pinfunction "80_80") (pintype "bidirectional"))
    )
    (net (code "191") (name "S23_N") (class "Default")
      (node (ref "U$2") (pin "A13") (pinfunction "OUT13_N_A13") (pintype "output"))
      (node (ref "X-SOUTH") (pin "83") (pinfunction "83_83") (pintype "bidirectional"))
    )
    (net (code "192") (name "S23_P") (class "Default")
      (node (ref "U$2") (pin "A14") (pinfunction "OUT13_P_A14") (pintype "output"))
      (node (ref "X-SOUTH") (pin "81") (pinfunction "81_81") (pintype "bidirectional"))
    )
    (net (code "193") (name "S24_N") (class "Default")
      (node (ref "U$2") (pin "C13") (pinfunction "OUT14_N_C13") (pintype "output"))
      (node (ref "X-SOUTH") (pin "88") (pinfunction "88_88") (pintype "bidirectional"))
    )
    (net (code "194") (name "S24_P") (class "Default")
      (node (ref "U$2") (pin "C14") (pinfunction "OUT14_P_C14") (pintype "output"))
      (node (ref "X-SOUTH") (pin "86") (pinfunction "86_86") (pintype "bidirectional"))
    )
    (net (code "195") (name "S25_N") (class "Default")
      (node (ref "U$2") (pin "B12") (pinfunction "OUT12_N_B12") (pintype "output"))
      (node (ref "X-SOUTH") (pin "89") (pinfunction "89_89") (pintype "bidirectional"))
    )
    (net (code "196") (name "S25_P") (class "Default")
      (node (ref "U$2") (pin "B13") (pinfunction "OUT12_P_B13") (pintype "output"))
      (node (ref "X-SOUTH") (pin "87") (pinfunction "87_87") (pintype "bidirectional"))
    )
    (net (code "197") (name "S26_N") (class "Default")
      (node (ref "U$2") (pin "D11") (pinfunction "OUT10_N_D11") (pintype "output"))
      (node (ref "X-SOUTH") (pin "94") (pinfunction "94_94") (pintype "bidirectional"))
    )
    (net (code "198") (name "S26_P") (class "Default")
      (node (ref "U$2") (pin "D12") (pinfunction "OUT10_P_D12") (pintype "output"))
      (node (ref "X-SOUTH") (pin "92") (pinfunction "92_92") (pintype "bidirectional"))
    )
    (net (code "199") (name "S27_N") (class "Default")
      (node (ref "U$2") (pin "A11") (pinfunction "OUT9_N_A11") (pintype "output"))
      (node (ref "X-SOUTH") (pin "95") (pinfunction "95_95") (pintype "bidirectional"))
    )
    (net (code "200") (name "S27_P") (class "Default")
      (node (ref "U$2") (pin "A12") (pinfunction "OUT9_P_A12") (pintype "output"))
      (node (ref "X-SOUTH") (pin "93") (pinfunction "93_93") (pintype "bidirectional"))
    )
    (net (code "201") (name "S28_N") (class "Default")
      (node (ref "U$2") (pin "C11") (pinfunction "OUT11_N_C11") (pintype "output"))
      (node (ref "X-SOUTH") (pin "100") (pinfunction "100_100") (pintype "bidirectional"))
    )
    (net (code "202") (name "S28_P") (class "Default")
      (node (ref "U$2") (pin "C12") (pinfunction "OUT11_P_C12") (pintype "output"))
      (node (ref "X-SOUTH") (pin "98") (pinfunction "98_98") (pintype "bidirectional"))
    )
    (net (code "203") (name "S29_N") (class "Default")
      (node (ref "U$2") (pin "B10") (pinfunction "OUT8_N_B10") (pintype "output"))
      (node (ref "X-SOUTH") (pin "101") (pinfunction "101_101") (pintype "bidirectional"))
    )
    (net (code "204") (name "S29_P") (class "Default")
      (node (ref "U$2") (pin "B11") (pinfunction "OUT8_P_B11") (pintype "output"))
      (node (ref "X-SOUTH") (pin "99") (pinfunction "99_99") (pintype "bidirectional"))
    )
    (net (code "205") (name "S30_N") (class "Default")
      (node (ref "U$2") (pin "C9") (pinfunction "OUT7_N_C9") (pintype "output"))
      (node (ref "X-SOUTH") (pin "106") (pinfunction "106_106") (pintype "bidirectional"))
    )
    (net (code "206") (name "S30_P") (class "Default")
      (node (ref "U$2") (pin "C10") (pinfunction "OUT7_P_C10") (pintype "output"))
      (node (ref "X-SOUTH") (pin "104") (pinfunction "104_104") (pintype "bidirectional"))
    )
    (net (code "207") (name "S31_N") (class "Default")
      (node (ref "U$2") (pin "B8") (pinfunction "OUT5_N_B8") (pintype "output"))
      (node (ref "X-SOUTH") (pin "107") (pinfunction "107_107") (pintype "bidirectional"))
    )
    (net (code "208") (name "S31_P") (class "Default")
      (node (ref "U$2") (pin "B9") (pinfunction "OUT5_P_B9") (pintype "output"))
      (node (ref "X-SOUTH") (pin "105") (pinfunction "105_105") (pintype "bidirectional"))
    )
    (net (code "209") (name "S32_N") (class "Default")
      (node (ref "U$2") (pin "D9") (pinfunction "OUT6_N_D9") (pintype "output"))
      (node (ref "X-SOUTH") (pin "112") (pinfunction "112_112") (pintype "bidirectional"))
    )
    (net (code "210") (name "S32_P") (class "Default")
      (node (ref "U$2") (pin "D10") (pinfunction "OUT6_P_D10") (pintype "output"))
      (node (ref "X-SOUTH") (pin "110") (pinfunction "110_110") (pintype "bidirectional"))
    )
    (net (code "211") (name "S33_N") (class "Default")
      (node (ref "U$2") (pin "A7") (pinfunction "OUT2_N_A7") (pintype "output"))
      (node (ref "X-SOUTH") (pin "113") (pinfunction "113_113") (pintype "bidirectional"))
    )
    (net (code "212") (name "S33_P") (class "Default")
      (node (ref "U$2") (pin "A8") (pinfunction "OUT2_P_A8") (pintype "output"))
      (node (ref "X-SOUTH") (pin "111") (pinfunction "111_111") (pintype "bidirectional"))
    )
    (net (code "213") (name "S34_N") (class "Default")
      (node (ref "U$2") (pin "C7") (pinfunction "OUT4_N_C7") (pintype "output"))
      (node (ref "X-SOUTH") (pin "118") (pinfunction "118_118") (pintype "bidirectional"))
    )
    (net (code "214") (name "S34_P") (class "Default")
      (node (ref "U$2") (pin "C8") (pinfunction "OUT4_P_C8") (pintype "output"))
      (node (ref "X-SOUTH") (pin "116") (pinfunction "116_116") (pintype "bidirectional"))
    )
    (net (code "215") (name "S35_N") (class "Default")
      (node (ref "U$2") (pin "B6") (pinfunction "OUT1_N_B6") (pintype "output"))
      (node (ref "X-SOUTH") (pin "119") (pinfunction "119_119") (pintype "bidirectional"))
    )
    (net (code "216") (name "S35_P") (class "Default")
      (node (ref "U$2") (pin "B7") (pinfunction "OUT1_P_B7") (pintype "output"))
      (node (ref "X-SOUTH") (pin "117") (pinfunction "117_117") (pintype "bidirectional"))
    )
    (net (code "217") (name "S36_N") (class "Default")
      (node (ref "U$2") (pin "D7") (pinfunction "OUT3_N_D7") (pintype "output"))
      (node (ref "X-SOUTH") (pin "124") (pinfunction "124_124") (pintype "bidirectional"))
    )
    (net (code "218") (name "S36_P") (class "Default")
      (node (ref "U$2") (pin "D8") (pinfunction "OUT3_P_D8") (pintype "output"))
      (node (ref "X-SOUTH") (pin "122") (pinfunction "122_122") (pintype "bidirectional"))
    )
    (net (code "219") (name "S37_N") (class "Default")
      (node (ref "U$2") (pin "A5") (pinfunction "OUTCTR_N_A5") (pintype "output"))
      (node (ref "X-SOUTH") (pin "125") (pinfunction "125_125") (pintype "bidirectional"))
    )
    (net (code "220") (name "S37_P") (class "Default")
      (node (ref "U$2") (pin "A6") (pinfunction "OUTCTR_P_A6") (pintype "output"))
      (node (ref "X-SOUTH") (pin "123") (pinfunction "123_123") (pintype "bidirectional"))
    )
    (net (code "221") (name "S38_N") (class "Default")
      (node (ref "X-SOUTH") (pin "130") (pinfunction "130_130") (pintype "bidirectional"))
    )
    (net (code "222") (name "S38_P") (class "Default")
      (node (ref "X-SOUTH") (pin "128") (pinfunction "128_128") (pintype "bidirectional"))
    )
    (net (code "223") (name "S39_N") (class "Default")
      (node (ref "U$4") (pin "6") (pinfunction "EN_6") (pintype "input"))
      (node (ref "X-SOUTH") (pin "131") (pinfunction "131_131") (pintype "bidirectional"))
    )
    (net (code "224") (name "S39_P") (class "Default")
      (node (ref "X-SOUTH") (pin "129") (pinfunction "129_129") (pintype "bidirectional"))
    )
    (net (code "225") (name "SPI_CLK") (class "Default")
      (node (ref "U$2") (pin "H29") (pinfunction "SPI_CLK_H29") (pintype "input"))
      (node (ref "U4") (pin "6") (pinfunction "1A1_6") (pintype "output"))
    )
    (net (code "226") (name "SPI_EN") (class "Default")
      (node (ref "U$2") (pin "F28") (pinfunction "SPI_EN_F28") (pintype "input"))
      (node (ref "U6") (pin "9") (pinfunction "B4_9") (pintype "bidirectional"))
    )
    (net (code "227") (name "SPI_IN") (class "Default")
      (node (ref "U$2") (pin "E28") (pinfunction "SPI_IN_E28") (pintype "input"))
      (node (ref "U4") (pin "7") (pinfunction "1A2_7") (pintype "output"))
    )
    (net (code "228") (name "SPI_OUT") (class "Default")
      (node (ref "U$2") (pin "G28") (pinfunction "SPI_OUT_G28") (pintype "output"))
      (node (ref "U4") (pin "8") (pinfunction "2A1_8") (pintype "output"))
    )
    (net (code "229") (name "SYS_RES_N") (class "Default")
      (node (ref "U$2") (pin "F30") (pinfunction "SYS_RES_N_F30") (pintype "input"))
      (node (ref "U5") (pin "10") (pinfunction "B3_10") (pintype "bidirectional"))
    )
    (net (code "230") (name "S_CHK_V") (class "Default")
      (node (ref "C5") (pin "1") (pinfunction "1_1") (pintype "passive"))
      (node (ref "C6") (pin "1") (pinfunction "1_1") (pintype "passive"))
      (node (ref "C7") (pin "1") (pinfunction "1_1") (pintype "passive"))
      (node (ref "R20") (pin "1") (pinfunction "1_1") (pintype "passive"))
      (node (ref "TP3") (pin "TP") (pinfunction "TP_TP") (pintype "input"))
      (node (ref "USE") (pin "8") (pinfunction "VDD_8") (pintype "power_in"))
      (node (ref "USS") (pin "8") (pinfunction "VDD_8") (pintype "power_in"))
      (node (ref "USW") (pin "8") (pinfunction "VDD_8") (pintype "power_in"))
      (node (ref "X-SOUTH") (pin "10") (pinfunction "10_10") (pintype "bidirectional"))
      (node (ref "X-SOUTH") (pin "8") (pinfunction "8_8") (pintype "bidirectional"))
    )
    (net (code "231") (name "S_I2C_V") (class "Default")
      (node (ref "X-SOUTH") (pin "135") (pinfunction "135_135") (pintype "bidirectional"))
      (node (ref "X-SOUTH") (pin "137") (pinfunction "137_137") (pintype "bidirectional"))
    )
    (net (code "232") (name "S_REF") (class "Default")
      (node (ref "R20") (pin "2") (pinfunction "2_2") (pintype "passive"))
      (node (ref "TP4") (pin "TP") (pinfunction "TP_TP") (pintype "input"))
      (node (ref "U2") (pin "3") (pinfunction "CATHODE_3") (pintype "output"))
      (node (ref "U2") (pin "4") (pinfunction "REF_4") (pintype "input"))
      (node (ref "USE") (pin "2") (pinfunction "VINA-_2") (pintype "input"))
      (node (ref "USE") (pin "5") (pinfunction "VINB+_5") (pintype "input"))
      (node (ref "USS") (pin "2") (pinfunction "VINA-_2") (pintype "input"))
      (node (ref "USS") (pin "5") (pinfunction "VINB+_5") (pintype "input"))
      (node (ref "USW") (pin "2") (pinfunction "VINA-_2") (pintype "input"))
      (node (ref "USW") (pin "5") (pinfunction "VINB+_5") (pintype "input"))
    )
    (net (code "233") (name "S_SCK") (class "Default")
      (node (ref "X-SOUTH") (pin "144") (pinfunction "144_144") (pintype "bidirectional"))
    )
    (net (code "234") (name "S_SCL") (class "Default")
      (node (ref "X-SOUTH") (pin "143") (pinfunction "143_143") (pintype "bidirectional"))
    )
    (net (code "235") (name "S_SDA") (class "Default")
      (node (ref "X-SOUTH") (pin "141") (pinfunction "141_141") (pintype "bidirectional"))
    )
    (net (code "236") (name "S_SDI") (class "Default")
      (node (ref "X-SOUTH") (pin "140") (pinfunction "140_140") (pintype "bidirectional"))
    )
    (net (code "237") (name "S_SDO") (class "Default")
      (node (ref "X-SOUTH") (pin "142") (pinfunction "142_142") (pintype "bidirectional"))
    )
    (net (code "238") (name "S_SPI_V") (class "Default")
      (node (ref "X-SOUTH") (pin "134") (pinfunction "134_134") (pintype "bidirectional"))
      (node (ref "X-SOUTH") (pin "136") (pinfunction "136_136") (pintype "bidirectional"))
    )
    (net (code "239") (name "S_VE") (class "Default")
      (node (ref "X-SOUTH") (pin "13") (pinfunction "13_13") (pintype "bidirectional"))
      (node (ref "X-SOUTH") (pin "19") (pinfunction "19_19") (pintype "bidirectional"))
      (node (ref "X-SOUTH") (pin "25") (pinfunction "25_25") (pintype "bidirectional"))
      (node (ref "X-SOUTH") (pin "31") (pinfunction "31_31") (pintype "bidirectional"))
      (node (ref "X-SOUTH") (pin "37") (pinfunction "37_37") (pintype "bidirectional"))
      (node (ref "X-SOUTH") (pin "43") (pinfunction "43_43") (pintype "bidirectional"))
    )
    (net (code "240") (name "S_VE_CV") (class "Default")
      (node (ref "C11") (pin "1") (pinfunction "1_1") (pintype "passive"))
      (node (ref "R10") (pin "1") (pinfunction "1_1") (pintype "passive"))
      (node (ref "X-SOUTH") (pin "2") (pinfunction "2_2") (pintype "bidirectional"))
    )
    (net (code "241") (name "S_VE_OV") (class "Default")
      (node (ref "USE") (pin "7") (pinfunction "OUTB_7") (pintype "output"))
      (node (ref "X-SOUTH") (pin "1") (pinfunction "1_1") (pintype "bidirectional"))
    )
    (net (code "242") (name "S_VE_UV") (class "Default")
      (node (ref "USE") (pin "1") (pinfunction "OUTA_1") (pintype "output"))
      (node (ref "X-SOUTH") (pin "7") (pinfunction "7_7") (pintype "bidirectional"))
    )
    (net (code "243") (name "S_VS") (class "Default")
      (node (ref "C45") (pin "1") (pinfunction "1_1") (pintype "passive"))
      (node (ref "C46") (pin "1") (pinfunction "1_1") (pintype "passive"))
      (node (ref "C47") (pin "1") (pinfunction "1_1") (pintype "passive"))
      (node (ref "C48") (pin "1") (pinfunction "1_1") (pintype "passive"))
      (node (ref "C49") (pin "1") (pinfunction "1_1") (pintype "passive"))
      (node (ref "C72") (pin "1") (pinfunction "1_1") (pintype "passive"))
      (node (ref "C73") (pin "1") (pinfunction "1_1") (pintype "passive"))
      (node (ref "C74") (pin "1") (pinfunction "1_1") (pintype "passive"))
      (node (ref "C81") (pin "1") (pinfunction "1_1") (pintype "passive"))
      (node (ref "C82") (pin "1") (pinfunction "1_1") (pintype "passive"))
      (node (ref "C83") (pin "1") (pinfunction "1_1") (pintype "passive"))
      (node (ref "TP6") (pin "TP") (pinfunction "TP_TP") (pintype "input"))
      (node (ref "U$2") (pin "A30") (pinfunction "VDD_PIX_A30") (pintype "power_in"))
      (node (ref "U$2") (pin "D28") (pinfunction "VDD_PIX_D28") (pintype "power_in"))
      (node (ref "U$2") (pin "D30") (pinfunction "VDD_PIX_D30") (pintype "power_in"))
      (node (ref "U$2") (pin "G1") (pinfunction "VDD_PIX_G1") (pintype "power_in"))
      (node (ref "U$2") (pin "H28") (pinfunction "VDD_PIX_H28") (pintype "power_in"))
      (node (ref "X-SOUTH") (pin "49") (pinfunction "49_49") (pintype "bidirectional"))
      (node (ref "X-SOUTH") (pin "55") (pinfunction "55_55") (pintype "bidirectional"))
      (node (ref "X-SOUTH") (pin "61") (pinfunction "61_61") (pintype "bidirectional"))
      (node (ref "X-SOUTH") (pin "67") (pinfunction "67_67") (pintype "bidirectional"))
      (node (ref "X-SOUTH") (pin "73") (pinfunction "73_73") (pintype "bidirectional"))
      (node (ref "X-SOUTH") (pin "79") (pinfunction "79_79") (pintype "bidirectional"))
      (node (ref "X-SOUTH") (pin "85") (pinfunction "85_85") (pintype "bidirectional"))
      (node (ref "X-SOUTH") (pin "91") (pinfunction "91_91") (pintype "bidirectional"))
      (node (ref "X-SOUTH") (pin "97") (pinfunction "97_97") (pintype "bidirectional"))
    )
    (net (code "244") (name "S_VS_CV") (class "Default")
      (node (ref "C12") (pin "1") (pinfunction "1_1") (pintype "passive"))
      (node (ref "R13") (pin "1") (pinfunction "1_1") (pintype "passive"))
      (node (ref "X-SOUTH") (pin "4") (pinfunction "4_4") (pintype "bidirectional"))
    )
    (net (code "245") (name "S_VS_OV") (class "Default")
      (node (ref "USS") (pin "7") (pinfunction "OUTB_7") (pintype "output"))
      (node (ref "X-SOUTH") (pin "3") (pinfunction "3_3") (pintype "bidirectional"))
    )
    (net (code "246") (name "S_VS_UV") (class "Default")
      (node (ref "USS") (pin "1") (pinfunction "OUTA_1") (pintype "output"))
      (node (ref "X-SOUTH") (pin "9") (pinfunction "9_9") (pintype "bidirectional"))
    )
    (net (code "247") (name "S_VW") (class "Default")
      (node (ref "C90") (pin "1") (pinfunction "1_1") (pintype "passive"))
      (node (ref "U$4") (pin "1") (pinfunction "BIAS_1") (pintype "power_in"))
      (node (ref "U$4") (pin "3") (pinfunction "IN_3") (pintype "power_in"))
      (node (ref "X-SOUTH") (pin "103") (pinfunction "103_103") (pintype "bidirectional"))
      (node (ref "X-SOUTH") (pin "109") (pinfunction "109_109") (pintype "bidirectional"))
      (node (ref "X-SOUTH") (pin "115") (pinfunction "115_115") (pintype "bidirectional"))
      (node (ref "X-SOUTH") (pin "121") (pinfunction "121_121") (pintype "bidirectional"))
      (node (ref "X-SOUTH") (pin "127") (pinfunction "127_127") (pintype "bidirectional"))
      (node (ref "X-SOUTH") (pin "133") (pinfunction "133_133") (pintype "bidirectional"))
    )
    (net (code "248") (name "S_VW_CV") (class "Default")
      (node (ref "C13") (pin "1") (pinfunction "1_1") (pintype "passive"))
      (node (ref "R16") (pin "1") (pinfunction "1_1") (pintype "passive"))
      (node (ref "X-SOUTH") (pin "6") (pinfunction "6_6") (pintype "bidirectional"))
    )
    (net (code "249") (name "S_VW_OV") (class "Default")
      (node (ref "USW") (pin "7") (pinfunction "OUTB_7") (pintype "output"))
      (node (ref "X-SOUTH") (pin "5") (pinfunction "5_5") (pintype "bidirectional"))
    )
    (net (code "250") (name "S_VW_UV") (class "Default")
      (node (ref "USW") (pin "1") (pinfunction "OUTA_1") (pintype "output"))
      (node (ref "X-SOUTH") (pin "11") (pinfunction "11_11") (pintype "bidirectional"))
    )
    (net (code "251") (name "TDIG1") (class "Default")
      (node (ref "U$2") (pin "G27") (pinfunction "TDIG1_G27") (pintype "output"))
      (node (ref "U5") (pin "9") (pinfunction "B4_9") (pintype "bidirectional"))
    )
    (net (code "252") (name "TDIG2") (class "Default")
      (node (ref "U$2") (pin "G26") (pinfunction "TDIG2_G26") (pintype "output"))
      (node (ref "U6") (pin "11") (pinfunction "B2_11") (pintype "bidirectional"))
    )
    (net (code "253") (name "T_EXP1") (class "Default")
      (node (ref "U$2") (pin "H30") (pinfunction "T_EXP1_H30") (pintype "input"))
      (node (ref "U5") (pin "12") (pinfunction "B1_12") (pintype "bidirectional"))
    )
    (net (code "254") (name "T_EXP2") (class "Default")
      (node (ref "U$2") (pin "E29") (pinfunction "T_EXP2_E29") (pintype "input"))
      (node (ref "U6") (pin "10") (pinfunction "B3_10") (pintype "bidirectional"))
    )
    (net (code "255") (name "VRAMP1") (class "Default")
      (node (ref "C16") (pin "1") (pinfunction "1_1") (pintype "passive"))
      (node (ref "R23") (pin "1") (pinfunction "1_1") (pintype "passive"))
      (node (ref "U$2") (pin "G29") (pinfunction "VRAMP1_G29") (pintype "bidirectional"))
    )
    (net (code "256") (name "VRAMP2") (class "Default")
      (node (ref "C17") (pin "1") (pinfunction "1_1") (pintype "passive"))
      (node (ref "R23") (pin "2") (pinfunction "2_2") (pintype "passive"))
      (node (ref "U$2") (pin "F29") (pinfunction "VRAMP2_F29") (pintype "bidirectional"))
    )
    (net (code "257") (name "VTREF") (class "Default")
      (node (ref "C65") (pin "1") (pinfunction "1_1") (pintype "passive"))
      (node (ref "C91") (pin "2") (pinfunction "2_2") (pintype "passive"))
      (node (ref "R21") (pin "2") (pinfunction "2_2") (pintype "passive"))
      (node (ref "R24") (pin "1") (pinfunction "1_1") (pintype "passive"))
      (node (ref "U$2") (pin "B2") (pinfunction "VTREF_B2") (pintype "bidirectional"))
      (node (ref "U$4") (pin "4") (pinfunction "OUT_4") (pintype "power_in"))
    )
    (net (code "258") (name "VTSIG") (class "Default")
      (node (ref "C66") (pin "1") (pinfunction "1_1") (pintype "passive"))
      (node (ref "R24") (pin "2") (pinfunction "2_2") (pintype "passive"))
      (node (ref "U$2") (pin "C2") (pinfunction "VTSIG_C2") (pintype "bidirectional"))
    )
    (net (code "259") (name "unconnected-(U1-NC-Pad1)") (class "Default")
      (node (ref "U1") (pin "1") (pinfunction "NC_1") (pintype "no_connect"))
    )
    (net (code "260") (name "unconnected-(U1-NC-Pad2)") (class "Default")
      (node (ref "U1") (pin "2") (pinfunction "NC_2") (pintype "no_connect"))
    )
    (net (code "261") (name "unconnected-(U2-NC-Pad1)") (class "Default")
      (node (ref "U2") (pin "1") (pinfunction "NC_1") (pintype "no_connect"))
    )
    (net (code "262") (name "unconnected-(U2-NC-Pad2)") (class "Default")
      (node (ref "U2") (pin "2") (pinfunction "NC_2") (pintype "no_connect"))
    )
    (net (code "263") (name "unconnected-(U4-2B2-Pad12)") (class "Default")
      (node (ref "U4") (pin "12") (pinfunction "2B2_12") (pintype "output"))
    )
    (net (code "264") (name "unconnected-(X-NORTH-PadM1)") (class "Default")
      (node (ref "X-NORTH") (pin "M1") (pinfunction "M1_M1") (pintype "bidirectional"))
    )
    (net (code "265") (name "unconnected-(X-NORTH-PadM2)") (class "Default")
      (node (ref "X-NORTH") (pin "M2") (pinfunction "M2_M2") (pintype "bidirectional"))
    )
    (net (code "266") (name "unconnected-(X-SOUTH-PadM1)") (class "Default")
      (node (ref "X-SOUTH") (pin "M1") (pinfunction "M1_M1") (pintype "bidirectional"))
    )
    (net (code "267") (name "unconnected-(X-SOUTH-PadM2)") (class "Default")
      (node (ref "X-SOUTH") (pin "M2") (pinfunction "M2_M2") (pintype "bidirectional"))
    )
  )
)
